# TSC8-75.net
KiCad netlist of a schematic drawn in EAGLE
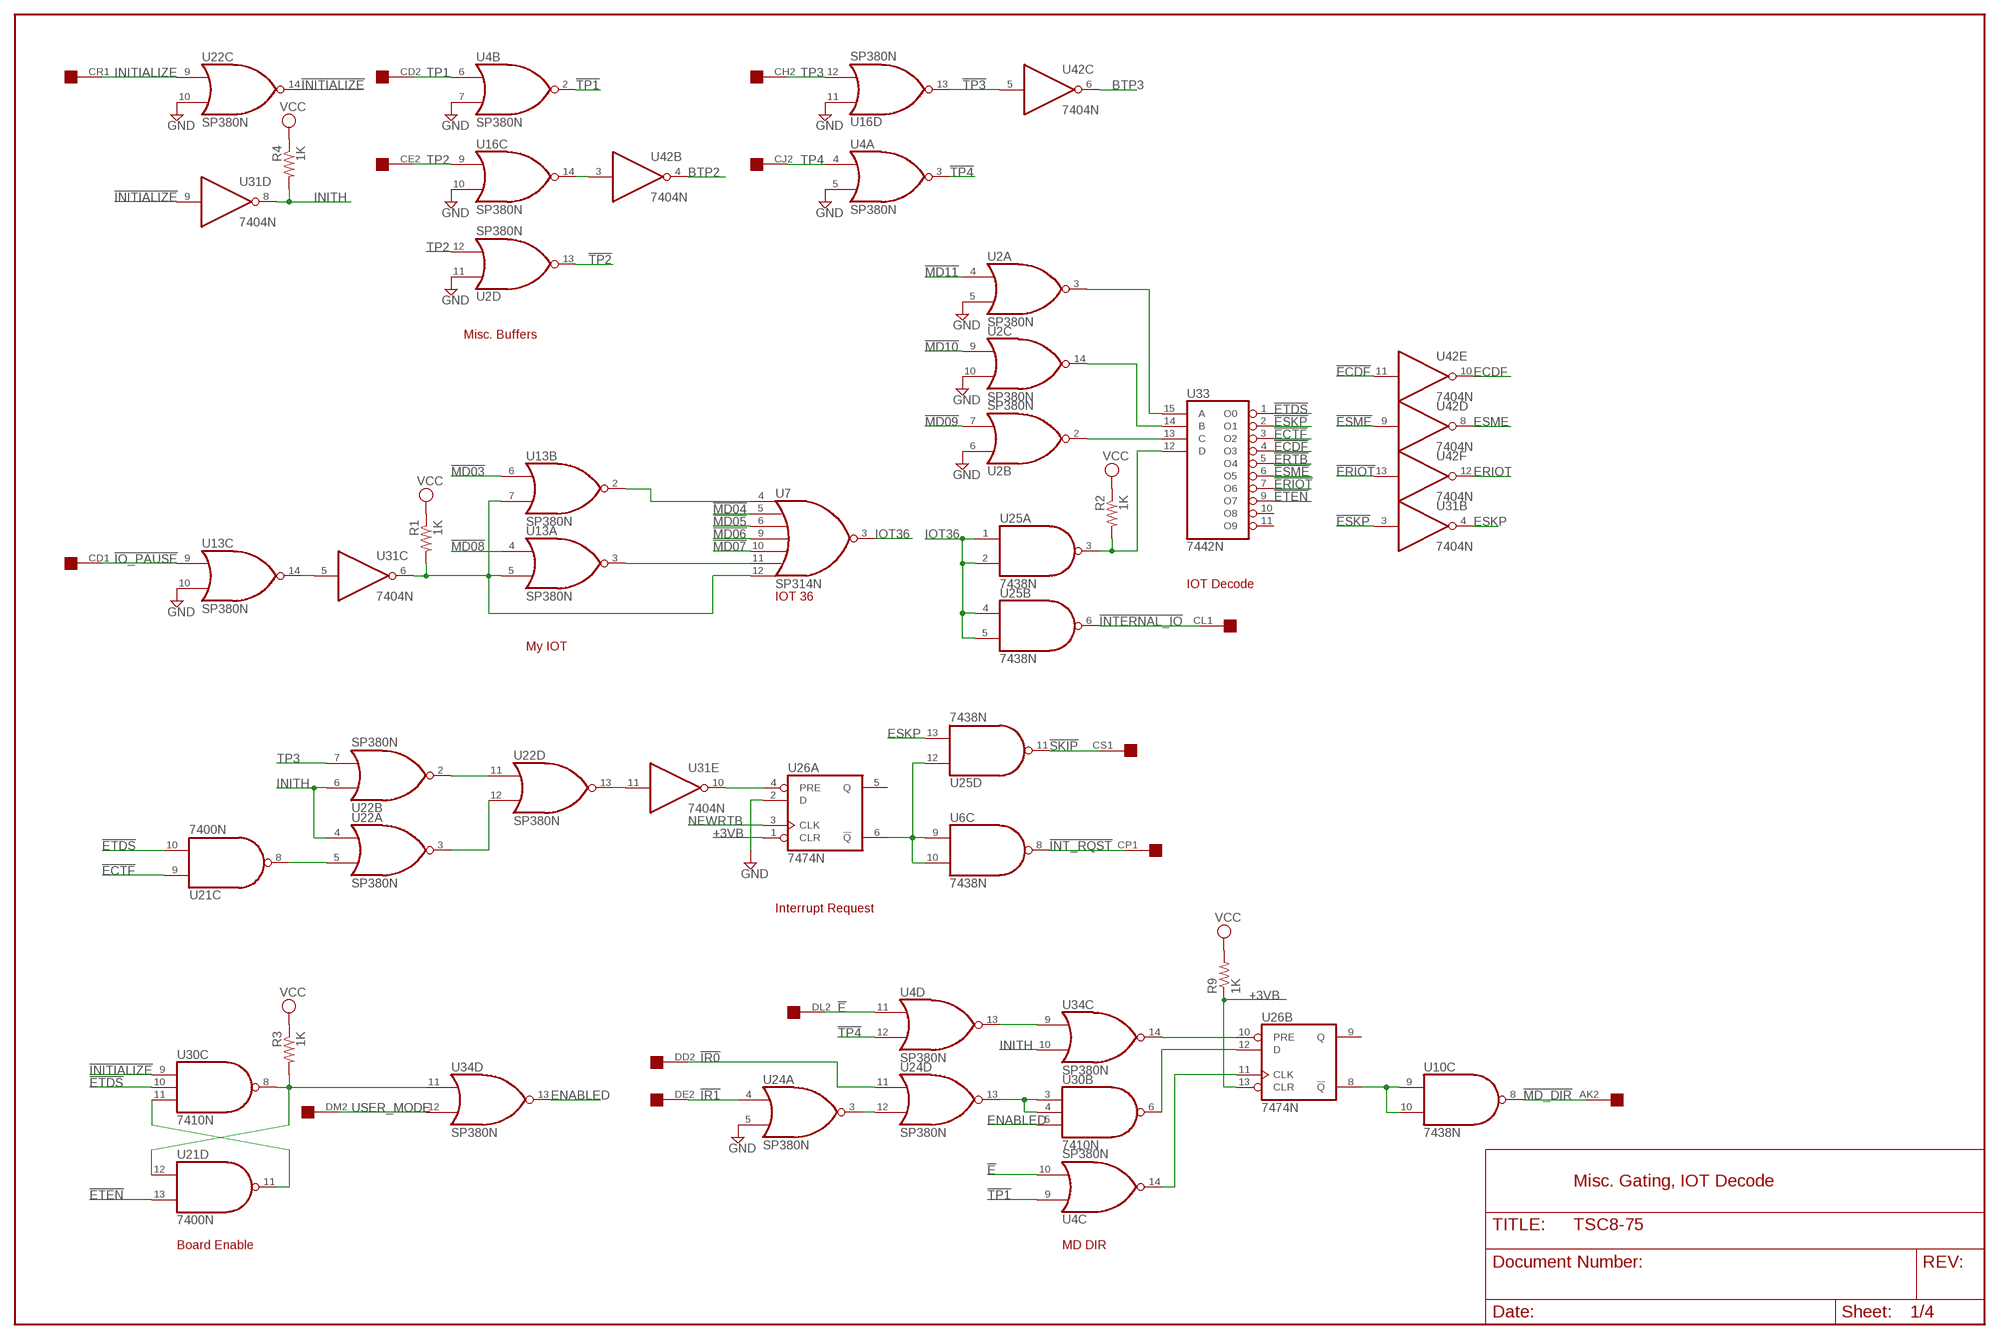
[diagram p0: schematic, sheet 1]
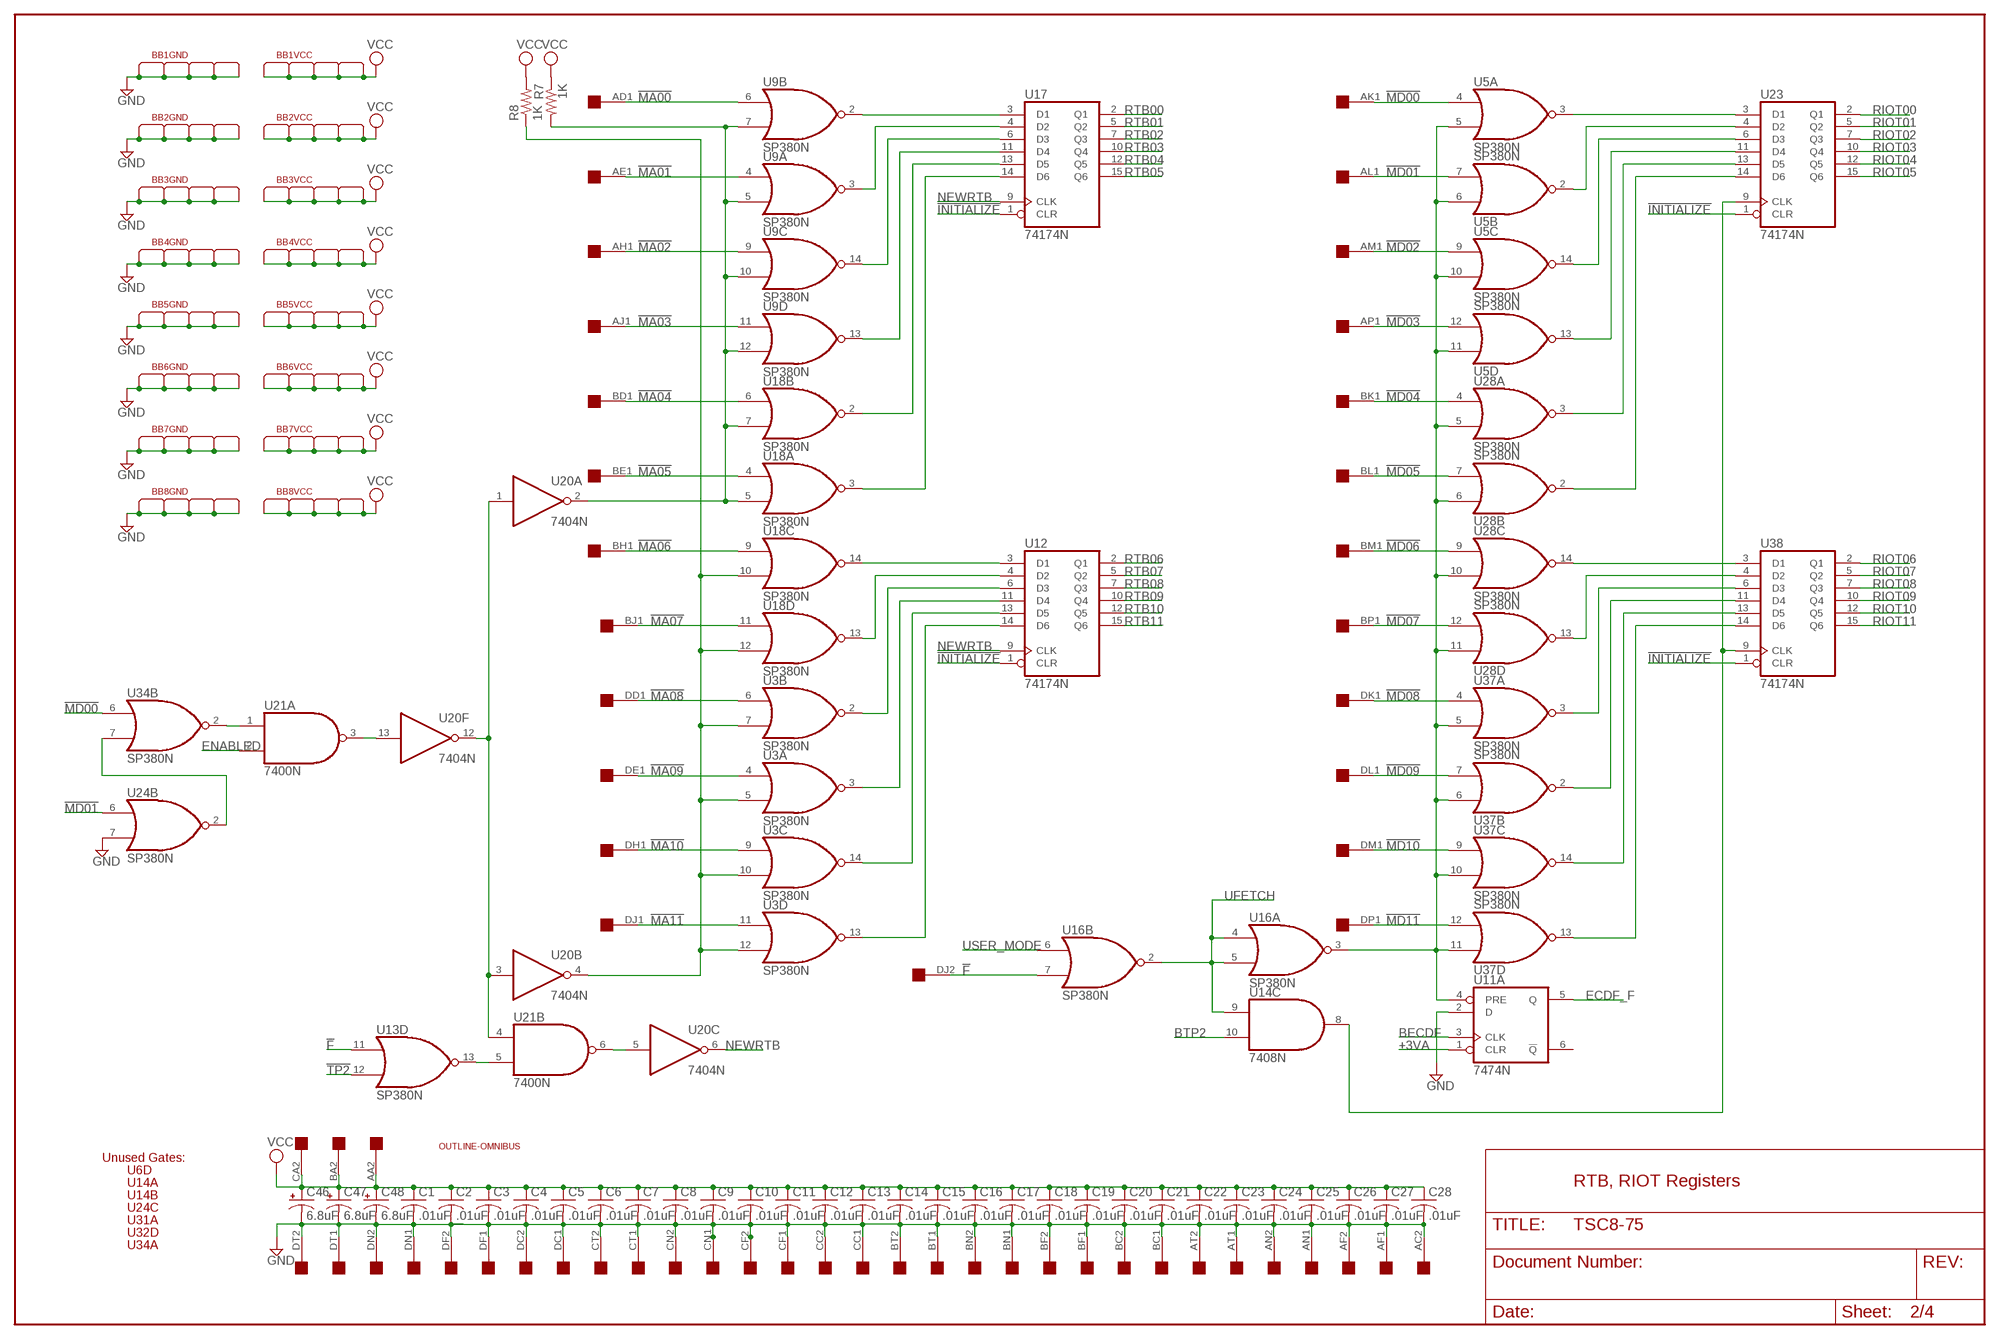
[diagram p1: schematic, sheet 2]
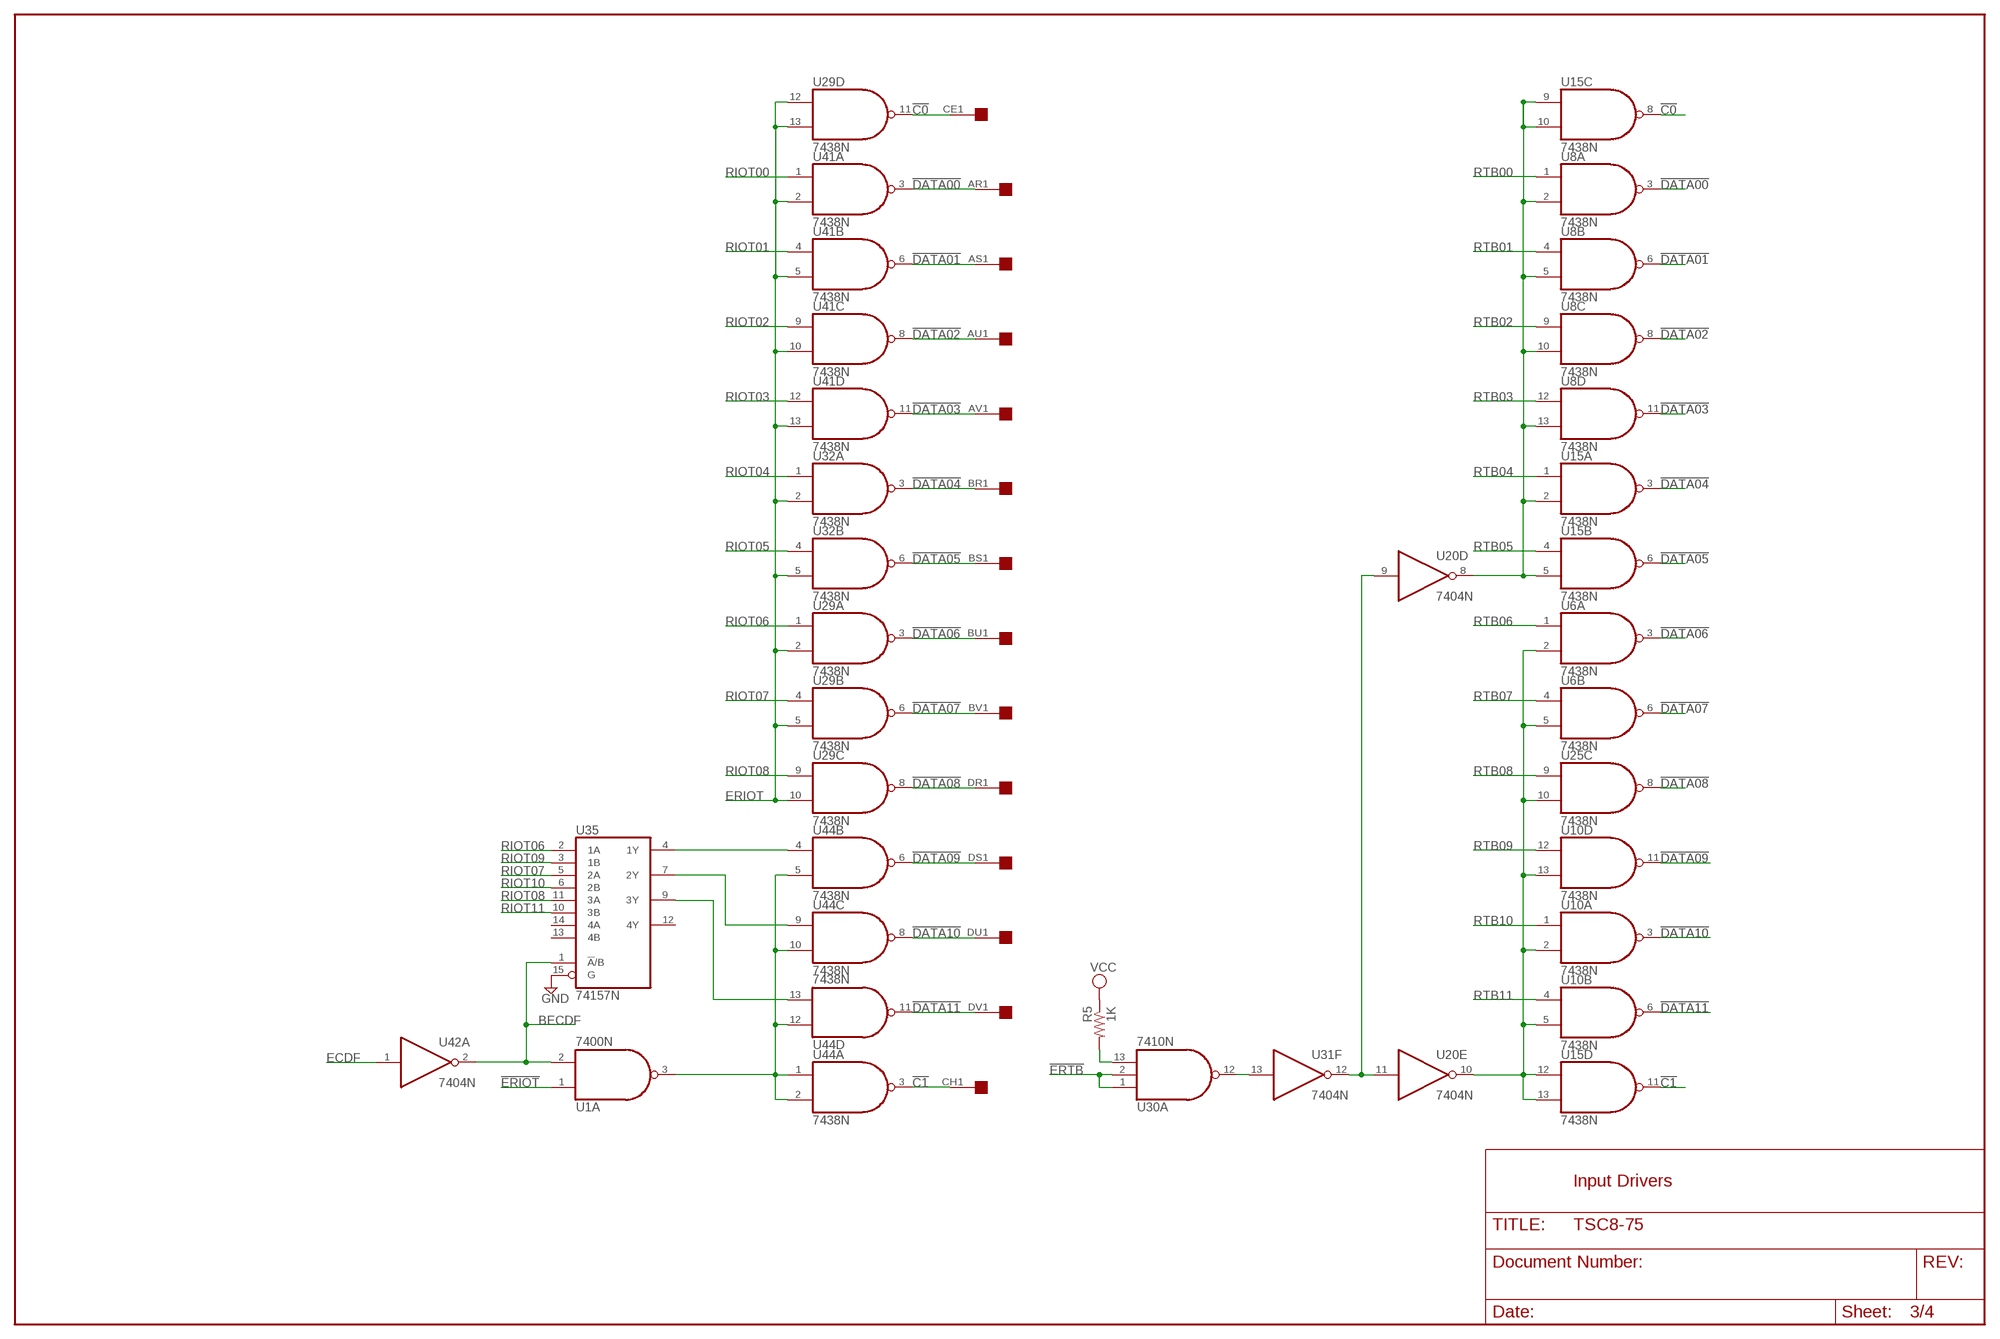
[diagram p2: schematic, sheet 3]
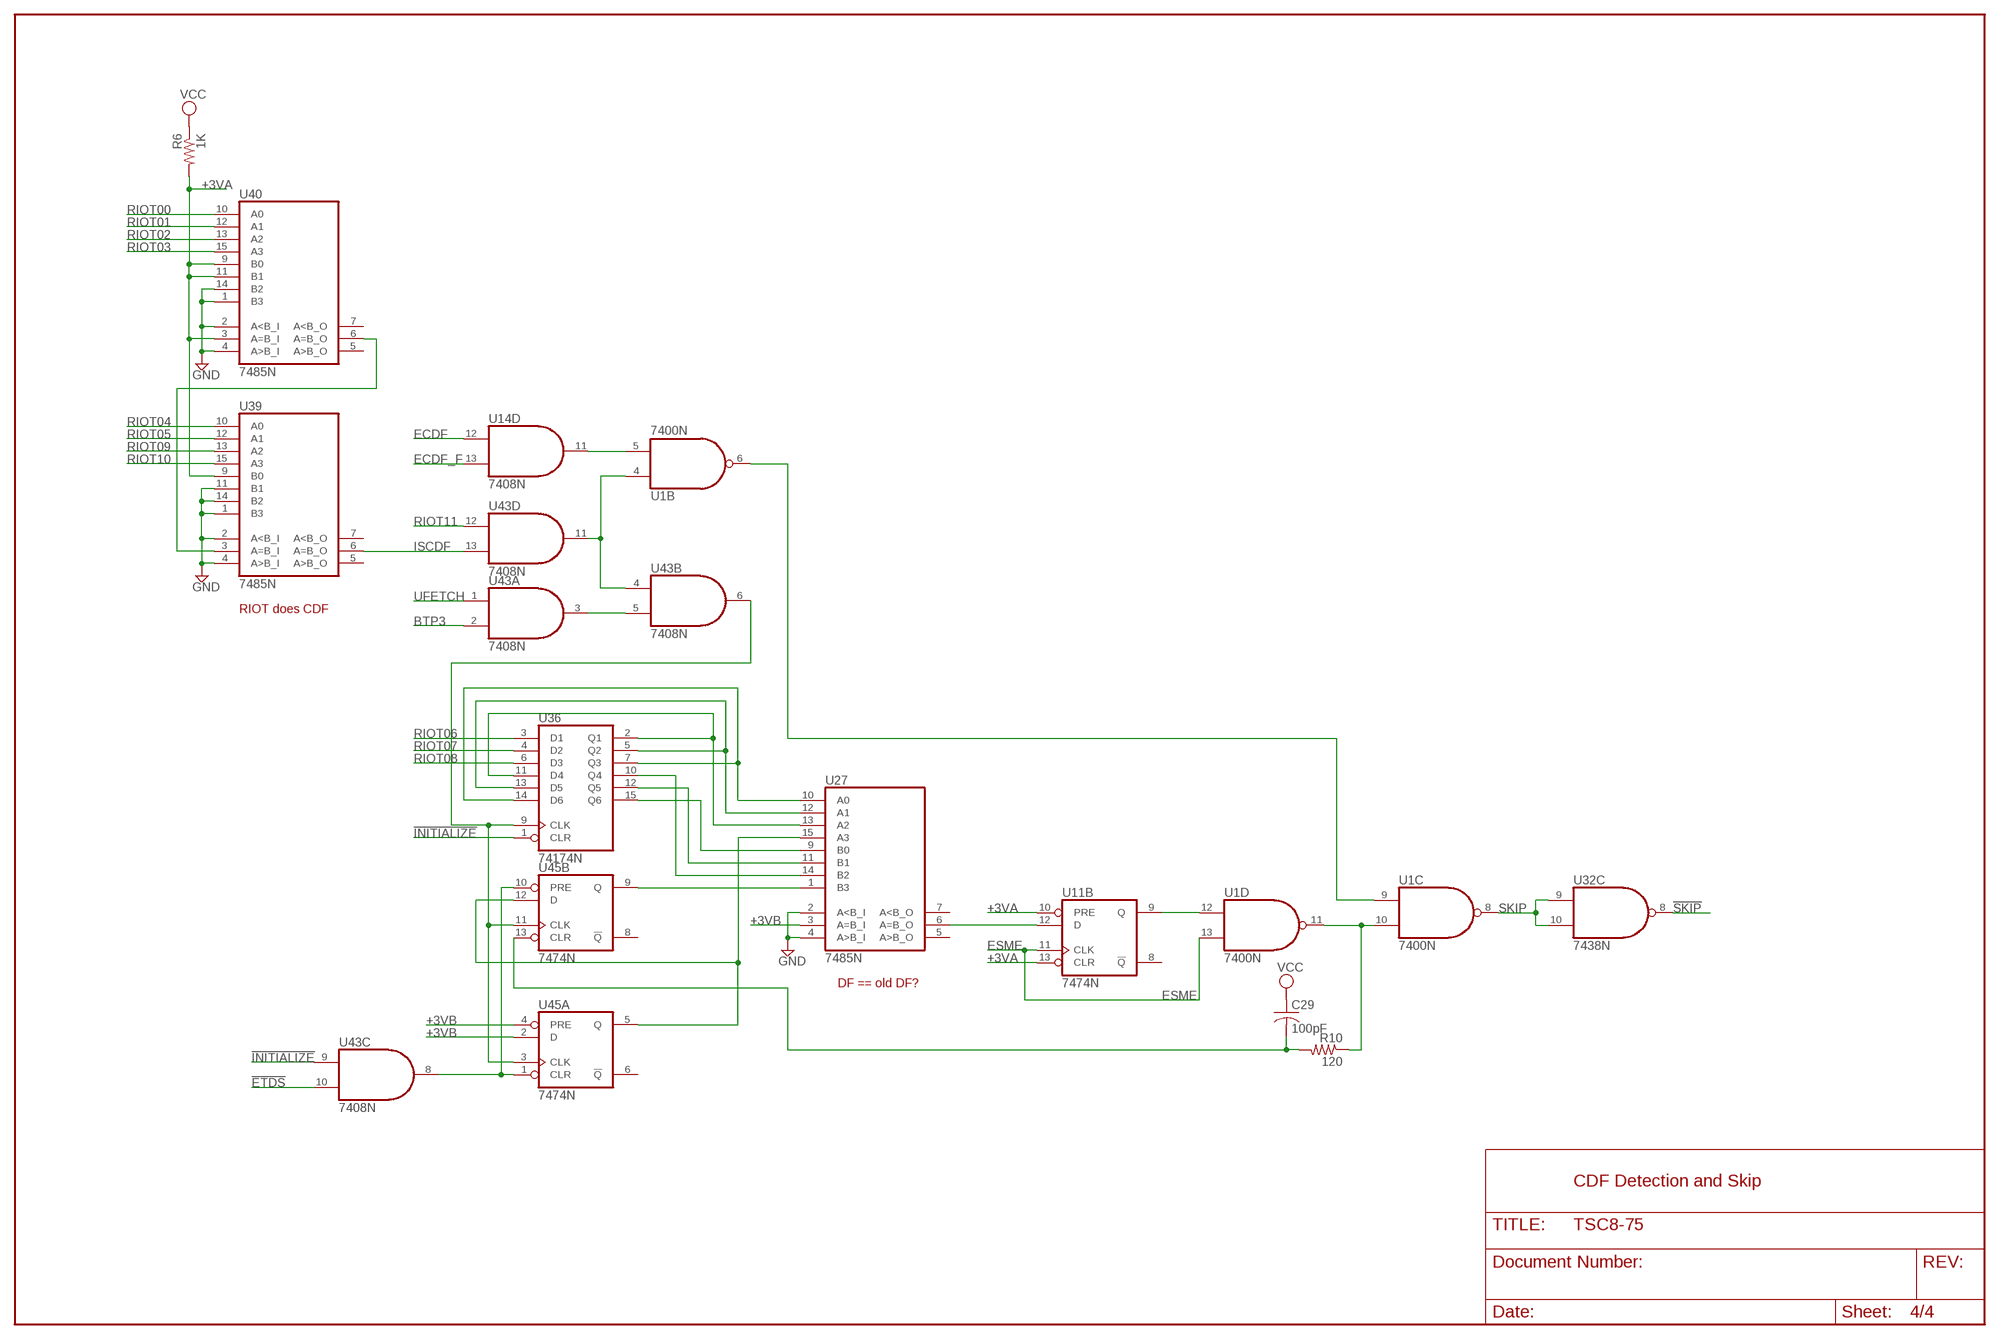
[diagram p3: schematic, sheet 4]

(export (version "E")
  (design (tool "Eeschema 10.0.6"))
  (components
    (comp (ref "BB1")
      (value "BUSBAR")
      (footprint "eagle-import:BUSBAR")
      (libsource (lib "eagle-import") (part "BUSBAR"))
    )
    (comp (ref "BB2")
      (value "BUSBAR")
      (footprint "eagle-import:BUSBAR")
      (libsource (lib "eagle-import") (part "BUSBAR"))
    )
    (comp (ref "BB3")
      (value "BUSBAR")
      (footprint "eagle-import:BUSBAR")
      (libsource (lib "eagle-import") (part "BUSBAR"))
    )
    (comp (ref "BB4")
      (value "BUSBAR")
      (footprint "eagle-import:BUSBAR")
      (libsource (lib "eagle-import") (part "BUSBAR"))
    )
    (comp (ref "BB5")
      (value "BUSBAR")
      (footprint "eagle-import:BUSBAR")
      (libsource (lib "eagle-import") (part "BUSBAR"))
    )
    (comp (ref "BB6")
      (value "BUSBAR")
      (footprint "eagle-import:BUSBAR")
      (libsource (lib "eagle-import") (part "BUSBAR"))
    )
    (comp (ref "BB7")
      (value "BUSBAR")
      (footprint "eagle-import:BUSBAR")
      (libsource (lib "eagle-import") (part "BUSBAR"))
    )
    (comp (ref "BB8")
      (value "BUSBAR")
      (footprint "eagle-import:BUSBAR")
      (libsource (lib "eagle-import") (part "BUSBAR"))
    )
    (comp (ref "C1")
      (value ".01uF")
      (footprint "eagle-import:C050-025X075")
      (libsource (lib "eagle-import") (part "C-US050-025X075"))
    )
    (comp (ref "C2")
      (value ".01uF")
      (footprint "eagle-import:C050-025X075")
      (libsource (lib "eagle-import") (part "C-US050-025X075"))
    )
    (comp (ref "C3")
      (value ".01uF")
      (footprint "eagle-import:C050-025X075")
      (libsource (lib "eagle-import") (part "C-US050-025X075"))
    )
    (comp (ref "C4")
      (value ".01uF")
      (footprint "eagle-import:C050-025X075")
      (libsource (lib "eagle-import") (part "C-US050-025X075"))
    )
    (comp (ref "C5")
      (value ".01uF")
      (footprint "eagle-import:C050-025X075")
      (libsource (lib "eagle-import") (part "C-US050-025X075"))
    )
    (comp (ref "C6")
      (value ".01uF")
      (footprint "eagle-import:C050-025X075")
      (libsource (lib "eagle-import") (part "C-US050-025X075"))
    )
    (comp (ref "C7")
      (value ".01uF")
      (footprint "eagle-import:C050-025X075")
      (libsource (lib "eagle-import") (part "C-US050-025X075"))
    )
    (comp (ref "C8")
      (value ".01uF")
      (footprint "eagle-import:C050-025X075")
      (libsource (lib "eagle-import") (part "C-US050-025X075"))
    )
    (comp (ref "C9")
      (value ".01uF")
      (footprint "eagle-import:C050-025X075")
      (libsource (lib "eagle-import") (part "C-US050-025X075"))
    )
    (comp (ref "C10")
      (value ".01uF")
      (footprint "eagle-import:C050-025X075")
      (libsource (lib "eagle-import") (part "C-US050-025X075"))
    )
    (comp (ref "C11")
      (value ".01uF")
      (footprint "eagle-import:C050-025X075")
      (libsource (lib "eagle-import") (part "C-US050-025X075"))
    )
    (comp (ref "C12")
      (value ".01uF")
      (footprint "eagle-import:C050-025X075")
      (libsource (lib "eagle-import") (part "C-US050-025X075"))
    )
    (comp (ref "C13")
      (value ".01uF")
      (footprint "eagle-import:C050-025X075")
      (libsource (lib "eagle-import") (part "C-US050-025X075"))
    )
    (comp (ref "C14")
      (value ".01uF")
      (footprint "eagle-import:C050-025X075")
      (libsource (lib "eagle-import") (part "C-US050-025X075"))
    )
    (comp (ref "C15")
      (value ".01uF")
      (footprint "eagle-import:C050-025X075")
      (libsource (lib "eagle-import") (part "C-US050-025X075"))
    )
    (comp (ref "C16")
      (value ".01uF")
      (footprint "eagle-import:C050-025X075")
      (libsource (lib "eagle-import") (part "C-US050-025X075"))
    )
    (comp (ref "C17")
      (value ".01uF")
      (footprint "eagle-import:C050-025X075")
      (libsource (lib "eagle-import") (part "C-US050-025X075"))
    )
    (comp (ref "C18")
      (value ".01uF")
      (footprint "eagle-import:C050-025X075")
      (libsource (lib "eagle-import") (part "C-US050-025X075"))
    )
    (comp (ref "C19")
      (value ".01uF")
      (footprint "eagle-import:C050-025X075")
      (libsource (lib "eagle-import") (part "C-US050-025X075"))
    )
    (comp (ref "C20")
      (value ".01uF")
      (footprint "eagle-import:C050-025X075")
      (libsource (lib "eagle-import") (part "C-US050-025X075"))
    )
    (comp (ref "C21")
      (value ".01uF")
      (footprint "eagle-import:C050-025X075")
      (libsource (lib "eagle-import") (part "C-US050-025X075"))
    )
    (comp (ref "C22")
      (value ".01uF")
      (footprint "eagle-import:C050-025X075")
      (libsource (lib "eagle-import") (part "C-US050-025X075"))
    )
    (comp (ref "C23")
      (value ".01uF")
      (footprint "eagle-import:C050-025X075")
      (libsource (lib "eagle-import") (part "C-US050-025X075"))
    )
    (comp (ref "C24")
      (value ".01uF")
      (footprint "eagle-import:C050-025X075")
      (libsource (lib "eagle-import") (part "C-US050-025X075"))
    )
    (comp (ref "C25")
      (value ".01uF")
      (footprint "eagle-import:C050-025X075")
      (libsource (lib "eagle-import") (part "C-US050-025X075"))
    )
    (comp (ref "C26")
      (value ".01uF")
      (footprint "eagle-import:C050-025X075")
      (libsource (lib "eagle-import") (part "C-US050-025X075"))
    )
    (comp (ref "C27")
      (value ".01uF")
      (footprint "eagle-import:C050-025X075")
      (libsource (lib "eagle-import") (part "C-US050-025X075"))
    )
    (comp (ref "C28")
      (value ".01uF")
      (footprint "eagle-import:C050-025X075")
      (libsource (lib "eagle-import") (part "C-US050-025X075"))
    )
    (comp (ref "C46")
      (value "6.8uF")
      (footprint "eagle-import:E12-8")
      (libsource (lib "eagle-import") (part "CPOL-USE20-8AXIAL"))
    )
    (comp (ref "C47")
      (value "6.8uF")
      (footprint "eagle-import:E12-8")
      (libsource (lib "eagle-import") (part "CPOL-USE20-8AXIAL"))
    )
    (comp (ref "C48")
      (value "6.8uF")
      (footprint "eagle-import:E12-8")
      (libsource (lib "eagle-import") (part "CPOL-USE20-8AXIAL"))
    )
    (comp (ref "EDGE")
      (value "edge")
      (footprint "eagle-import:EDGE-CON8")
      (libsource (lib "eagle-import") (part "QUAD"))
    )
    (comp (ref "R7")
      (value "1K")
      (footprint "eagle-import:0204_7")
      (libsource (lib "eagle-import") (part "R-US_0204/7"))
    )
    (comp (ref "R8")
      (value "1K")
      (footprint "eagle-import:0204_7")
      (libsource (lib "eagle-import") (part "R-US_0204/7"))
    )
    (comp (ref "U$1")
      (value "OUTLINE-OMNIBUS")
      (footprint "eagle-import:OMNIBUS")
      (libsource (lib "eagle-import") (part "OUTLINE-OMNIBUS"))
    )
    (comp (ref "U3")
      (value "SP380N")
      (footprint "eagle-import:DIL14")
      (libsource (lib "eagle-import") (part "SP380N"))
    )
    (comp (ref "U5")
      (value "SP380N")
      (footprint "eagle-import:DIL14")
      (libsource (lib "eagle-import") (part "SP380N"))
    )
    (comp (ref "U9")
      (value "SP380N")
      (footprint "eagle-import:DIL14")
      (libsource (lib "eagle-import") (part "SP380N"))
    )
    (comp (ref "U11")
      (value "7474N")
      (footprint "eagle-import:DIL14")
      (libsource (lib "eagle-import") (part "7474NS"))
    )
    (comp (ref "U12")
      (value "74174N")
      (footprint "eagle-import:DIL16")
      (libsource (lib "eagle-import") (part "74174N"))
    )
    (comp (ref "U13")
      (value "SP380N")
      (footprint "eagle-import:DIL14")
      (libsource (lib "eagle-import") (part "SP380N"))
    )
    (comp (ref "U14")
      (value "7408N")
      (footprint "eagle-import:DIL14")
      (libsource (lib "eagle-import") (part "7408NS"))
    )
    (comp (ref "U16")
      (value "SP380N")
      (footprint "eagle-import:DIL14")
      (libsource (lib "eagle-import") (part "SP380N"))
    )
    (comp (ref "U17")
      (value "74174N")
      (footprint "eagle-import:DIL16")
      (libsource (lib "eagle-import") (part "74174N"))
    )
    (comp (ref "U18")
      (value "SP380N")
      (footprint "eagle-import:DIL14")
      (libsource (lib "eagle-import") (part "SP380N"))
    )
    (comp (ref "U20")
      (value "7404N")
      (footprint "eagle-import:DIL14")
      (libsource (lib "eagle-import") (part "7404N"))
    )
    (comp (ref "U21")
      (value "7400N")
      (footprint "eagle-import:DIL14")
      (libsource (lib "eagle-import") (part "7400N"))
    )
    (comp (ref "U23")
      (value "74174N")
      (footprint "eagle-import:DIL16")
      (libsource (lib "eagle-import") (part "74174N"))
    )
    (comp (ref "U24")
      (value "SP380N")
      (footprint "eagle-import:DIL14")
      (libsource (lib "eagle-import") (part "SP380N"))
    )
    (comp (ref "U28")
      (value "SP380N")
      (footprint "eagle-import:DIL14")
      (libsource (lib "eagle-import") (part "SP380N"))
    )
    (comp (ref "U34")
      (value "SP380N")
      (footprint "eagle-import:DIL14")
      (libsource (lib "eagle-import") (part "SP380N"))
    )
    (comp (ref "U37")
      (value "SP380N")
      (footprint "eagle-import:DIL14")
      (libsource (lib "eagle-import") (part "SP380N"))
    )
    (comp (ref "U38")
      (value "74174N")
      (footprint "eagle-import:DIL16")
      (libsource (lib "eagle-import") (part "74174N"))
    )
    (comp (ref "C29")
      (value "100pF")
      (footprint "eagle-import:C050-025X075")
      (libsource (lib "eagle-import") (part "C-US050-025X075"))
    )
    (comp (ref "R6")
      (value "1K")
      (footprint "eagle-import:0204_7")
      (libsource (lib "eagle-import") (part "R-US_0204/7"))
    )
    (comp (ref "R10")
      (value "120")
      (footprint "eagle-import:0204_7")
      (libsource (lib "eagle-import") (part "R-US_0204/7"))
    )
    (comp (ref "U1")
      (value "7400N")
      (footprint "eagle-import:DIL14")
      (libsource (lib "eagle-import") (part "7400N"))
    )
    (comp (ref "U27")
      (value "7485N")
      (footprint "eagle-import:DIL16")
      (libsource (lib "eagle-import") (part "7485N"))
    )
    (comp (ref "U32")
      (value "7438N")
      (footprint "eagle-import:DIL14")
      (libsource (lib "eagle-import") (part "7438N"))
    )
    (comp (ref "U36")
      (value "74174N")
      (footprint "eagle-import:DIL16")
      (libsource (lib "eagle-import") (part "74174N"))
    )
    (comp (ref "U39")
      (value "7485N")
      (footprint "eagle-import:DIL16")
      (libsource (lib "eagle-import") (part "7485N"))
    )
    (comp (ref "U40")
      (value "7485N")
      (footprint "eagle-import:DIL16")
      (libsource (lib "eagle-import") (part "7485N"))
    )
    (comp (ref "U43")
      (value "7408N")
      (footprint "eagle-import:DIL14")
      (libsource (lib "eagle-import") (part "7408NS"))
    )
    (comp (ref "U45")
      (value "7474N")
      (footprint "eagle-import:DIL14")
      (libsource (lib "eagle-import") (part "7474NS"))
    )
    (comp (ref "R1")
      (value "1K")
      (footprint "eagle-import:0204_7")
      (libsource (lib "eagle-import") (part "R-US_0204/7"))
    )
    (comp (ref "R2")
      (value "1K")
      (footprint "eagle-import:0204_7")
      (libsource (lib "eagle-import") (part "R-US_0204/7"))
    )
    (comp (ref "R3")
      (value "1K")
      (footprint "eagle-import:0204_7")
      (libsource (lib "eagle-import") (part "R-US_0204/7"))
    )
    (comp (ref "R4")
      (value "1K")
      (footprint "eagle-import:0204_7")
      (libsource (lib "eagle-import") (part "R-US_0204/7"))
    )
    (comp (ref "R9")
      (value "1K")
      (footprint "eagle-import:0204_7")
      (libsource (lib "eagle-import") (part "R-US_0204/7"))
    )
    (comp (ref "U2")
      (value "SP380N")
      (footprint "eagle-import:DIL14")
      (libsource (lib "eagle-import") (part "SP380N"))
    )
    (comp (ref "U4")
      (value "SP380N")
      (footprint "eagle-import:DIL14")
      (libsource (lib "eagle-import") (part "SP380N"))
    )
    (comp (ref "U6")
      (value "7438N")
      (footprint "eagle-import:DIL14")
      (libsource (lib "eagle-import") (part "7438N"))
    )
    (comp (ref "U7")
      (value "SP314N")
      (footprint "eagle-import:DIL14")
      (libsource (lib "eagle-import") (part "SP314N"))
    )
    (comp (ref "U10")
      (value "7438N")
      (footprint "eagle-import:DIL14")
      (libsource (lib "eagle-import") (part "7438N"))
    )
    (comp (ref "U22")
      (value "SP380N")
      (footprint "eagle-import:DIL14")
      (libsource (lib "eagle-import") (part "SP380N"))
    )
    (comp (ref "U25")
      (value "7438N")
      (footprint "eagle-import:DIL14")
      (libsource (lib "eagle-import") (part "7438N"))
    )
    (comp (ref "U26")
      (value "7474N")
      (footprint "eagle-import:DIL14")
      (libsource (lib "eagle-import") (part "7474NS"))
    )
    (comp (ref "U30")
      (value "7410N")
      (footprint "eagle-import:DIL14")
      (libsource (lib "eagle-import") (part "7410N"))
    )
    (comp (ref "U31")
      (value "7404N")
      (footprint "eagle-import:DIL14")
      (libsource (lib "eagle-import") (part "7404N"))
    )
    (comp (ref "U33")
      (value "7442N")
      (footprint "eagle-import:DIL16")
      (libsource (lib "eagle-import") (part "7442NLS"))
    )
    (comp (ref "U42")
      (value "7404N")
      (footprint "eagle-import:DIL14")
      (libsource (lib "eagle-import") (part "7404N"))
    )
    (comp (ref "R5")
      (value "1K")
      (footprint "eagle-import:0204_7")
      (libsource (lib "eagle-import") (part "R-US_0204/7"))
    )
    (comp (ref "U8")
      (value "7438N")
      (footprint "eagle-import:DIL14")
      (libsource (lib "eagle-import") (part "7438N"))
    )
    (comp (ref "U15")
      (value "7438N")
      (footprint "eagle-import:DIL14")
      (libsource (lib "eagle-import") (part "7438N"))
    )
    (comp (ref "U29")
      (value "7438N")
      (footprint "eagle-import:DIL14")
      (libsource (lib "eagle-import") (part "7438N"))
    )
    (comp (ref "U35")
      (value "74157N")
      (footprint "eagle-import:DIL16")
      (libsource (lib "eagle-import") (part "74157N"))
    )
    (comp (ref "U41")
      (value "7438N")
      (footprint "eagle-import:DIL14")
      (libsource (lib "eagle-import") (part "7438N"))
    )
    (comp (ref "U44")
      (value "7438N")
      (footprint "eagle-import:DIL14")
      (libsource (lib "eagle-import") (part "7438N"))
    )
  )
  (nets
    (net (code "1") (name "+3VA") (class "Default")
      (node (ref "R6") (pin "2") (pinfunction "2_2") (pintype "passive"))
      (node (ref "U11") (pin "1") (pinfunction "CLR_1") (pintype "input"))
      (node (ref "U11") (pin "10") (pinfunction "PRE_10") (pintype "input"))
      (node (ref "U11") (pin "13") (pinfunction "CLR_13") (pintype "input"))
      (node (ref "U39") (pin "9") (pinfunction "B0_9") (pintype "input"))
      (node (ref "U40") (pin "11") (pinfunction "B1_11") (pintype "input"))
      (node (ref "U40") (pin "3") (pinfunction "A=B_I_3") (pintype "input"))
      (node (ref "U40") (pin "9") (pinfunction "B0_9") (pintype "input"))
    )
    (net (code "2") (name "+3VB") (class "Default")
      (node (ref "R9") (pin "1") (pinfunction "1_1") (pintype "passive"))
      (node (ref "U26") (pin "1") (pinfunction "CLR_1") (pintype "input"))
      (node (ref "U26") (pin "13") (pinfunction "CLR_13") (pintype "input"))
      (node (ref "U27") (pin "3") (pinfunction "A=B_I_3") (pintype "input"))
      (node (ref "U45") (pin "2") (pinfunction "D_2") (pintype "input"))
      (node (ref "U45") (pin "4") (pinfunction "PRE_4") (pintype "input"))
    )
    (net (code "3") (name "BECDF") (class "Default")
      (node (ref "U1") (pin "2") (pinfunction "I1_2") (pintype "input"))
      (node (ref "U11") (pin "3") (pinfunction "CLK_3") (pintype "input"))
      (node (ref "U35") (pin "1") (pinfunction "~{A}/B_1") (pintype "input"))
      (node (ref "U42") (pin "2") (pinfunction "O_2") (pintype "output"))
    )
    (net (code "4") (name "BTP2") (class "Default")
      (node (ref "U14") (pin "10") (pinfunction "I1_10") (pintype "input"))
      (node (ref "U42") (pin "4") (pinfunction "O_4") (pintype "output"))
    )
    (net (code "5") (name "BTP3") (class "Default")
      (node (ref "U42") (pin "6") (pinfunction "O_6") (pintype "output"))
      (node (ref "U43") (pin "2") (pinfunction "I1_2") (pintype "input"))
    )
    (net (code "6") (name "ECDF") (class "Default")
      (node (ref "U14") (pin "12") (pinfunction "I0_12") (pintype "input"))
      (node (ref "U42") (pin "1") (pinfunction "I_1") (pintype "input"))
      (node (ref "U42") (pin "10") (pinfunction "O_10") (pintype "output"))
    )
    (net (code "7") (name "ECDF_F") (class "Default")
      (node (ref "U11") (pin "5") (pinfunction "Q_5") (pintype "output"))
      (node (ref "U14") (pin "13") (pinfunction "I1_13") (pintype "input"))
    )
    (net (code "8") (name "ENABLED") (class "Default")
      (node (ref "U21") (pin "2") (pinfunction "I1_2") (pintype "input"))
      (node (ref "U30") (pin "5") (pinfunction "I2_5") (pintype "input"))
      (node (ref "U34") (pin "13") (pinfunction "O_13") (pintype "output"))
    )
    (net (code "9") (name "ERIOT") (class "Default")
      (node (ref "U29") (pin "10") (pinfunction "I1_10") (pintype "input"))
      (node (ref "U29") (pin "12") (pinfunction "I0_12") (pintype "input"))
      (node (ref "U29") (pin "13") (pinfunction "I1_13") (pintype "input"))
      (node (ref "U29") (pin "2") (pinfunction "I1_2") (pintype "input"))
      (node (ref "U29") (pin "5") (pinfunction "I1_5") (pintype "input"))
      (node (ref "U32") (pin "2") (pinfunction "I1_2") (pintype "input"))
      (node (ref "U32") (pin "5") (pinfunction "I1_5") (pintype "input"))
      (node (ref "U41") (pin "10") (pinfunction "I1_10") (pintype "input"))
      (node (ref "U41") (pin "13") (pinfunction "I1_13") (pintype "input"))
      (node (ref "U41") (pin "2") (pinfunction "I1_2") (pintype "input"))
      (node (ref "U41") (pin "5") (pinfunction "I1_5") (pintype "input"))
      (node (ref "U42") (pin "12") (pinfunction "O_12") (pintype "output"))
    )
    (net (code "10") (name "ESKP") (class "Default")
      (node (ref "U25") (pin "13") (pinfunction "I1_13") (pintype "input"))
      (node (ref "U31") (pin "4") (pinfunction "O_4") (pintype "output"))
    )
    (net (code "11") (name "ESME") (class "Default")
      (node (ref "U1") (pin "13") (pinfunction "I1_13") (pintype "input"))
      (node (ref "U11") (pin "11") (pinfunction "CLK_11") (pintype "input"))
      (node (ref "U42") (pin "8") (pinfunction "O_8") (pintype "output"))
    )
    (net (code "12") (name "GND") (class "Default")
      (node (ref "BB1") (pin "GND1") (pinfunction "1_GND1") (pintype "passive"))
      (node (ref "BB1") (pin "GND2") (pinfunction "2_GND2") (pintype "passive"))
      (node (ref "BB1") (pin "GND3") (pinfunction "3_GND3") (pintype "passive"))
      (node (ref "BB1") (pin "GND4") (pinfunction "4_GND4") (pintype "passive"))
      (node (ref "BB1") (pin "GND5") (pinfunction "5_GND5") (pintype "passive"))
      (node (ref "BB2") (pin "GND1") (pinfunction "1_GND1") (pintype "passive"))
      (node (ref "BB2") (pin "GND2") (pinfunction "2_GND2") (pintype "passive"))
      (node (ref "BB2") (pin "GND3") (pinfunction "3_GND3") (pintype "passive"))
      (node (ref "BB2") (pin "GND4") (pinfunction "4_GND4") (pintype "passive"))
      (node (ref "BB2") (pin "GND5") (pinfunction "5_GND5") (pintype "passive"))
      (node (ref "BB3") (pin "GND1") (pinfunction "1_GND1") (pintype "passive"))
      (node (ref "BB3") (pin "GND2") (pinfunction "2_GND2") (pintype "passive"))
      (node (ref "BB3") (pin "GND3") (pinfunction "3_GND3") (pintype "passive"))
      (node (ref "BB3") (pin "GND4") (pinfunction "4_GND4") (pintype "passive"))
      (node (ref "BB3") (pin "GND5") (pinfunction "5_GND5") (pintype "passive"))
      (node (ref "BB4") (pin "GND1") (pinfunction "1_GND1") (pintype "passive"))
      (node (ref "BB4") (pin "GND2") (pinfunction "2_GND2") (pintype "passive"))
      (node (ref "BB4") (pin "GND3") (pinfunction "3_GND3") (pintype "passive"))
      (node (ref "BB4") (pin "GND4") (pinfunction "4_GND4") (pintype "passive"))
      (node (ref "BB4") (pin "GND5") (pinfunction "5_GND5") (pintype "passive"))
      (node (ref "BB5") (pin "GND1") (pinfunction "1_GND1") (pintype "passive"))
      (node (ref "BB5") (pin "GND2") (pinfunction "2_GND2") (pintype "passive"))
      (node (ref "BB5") (pin "GND3") (pinfunction "3_GND3") (pintype "passive"))
      (node (ref "BB5") (pin "GND4") (pinfunction "4_GND4") (pintype "passive"))
      (node (ref "BB5") (pin "GND5") (pinfunction "5_GND5") (pintype "passive"))
      (node (ref "BB6") (pin "GND1") (pinfunction "1_GND1") (pintype "passive"))
      (node (ref "BB6") (pin "GND2") (pinfunction "2_GND2") (pintype "passive"))
      (node (ref "BB6") (pin "GND3") (pinfunction "3_GND3") (pintype "passive"))
      (node (ref "BB6") (pin "GND4") (pinfunction "4_GND4") (pintype "passive"))
      (node (ref "BB6") (pin "GND5") (pinfunction "5_GND5") (pintype "passive"))
      (node (ref "BB7") (pin "GND1") (pinfunction "1_GND1") (pintype "passive"))
      (node (ref "BB7") (pin "GND2") (pinfunction "2_GND2") (pintype "passive"))
      (node (ref "BB7") (pin "GND3") (pinfunction "3_GND3") (pintype "passive"))
      (node (ref "BB7") (pin "GND4") (pinfunction "4_GND4") (pintype "passive"))
      (node (ref "BB7") (pin "GND5") (pinfunction "5_GND5") (pintype "passive"))
      (node (ref "BB8") (pin "GND1") (pinfunction "1_GND1") (pintype "passive"))
      (node (ref "BB8") (pin "GND2") (pinfunction "2_GND2") (pintype "passive"))
      (node (ref "BB8") (pin "GND3") (pinfunction "3_GND3") (pintype "passive"))
      (node (ref "BB8") (pin "GND4") (pinfunction "4_GND4") (pintype "passive"))
      (node (ref "BB8") (pin "GND5") (pinfunction "5_GND5") (pintype "passive"))
      (node (ref "C1") (pin "2") (pinfunction "2_2") (pintype "passive"))
      (node (ref "C10") (pin "2") (pinfunction "2_2") (pintype "passive"))
      (node (ref "C11") (pin "2") (pinfunction "2_2") (pintype "passive"))
      (node (ref "C12") (pin "2") (pinfunction "2_2") (pintype "passive"))
      (node (ref "C13") (pin "2") (pinfunction "2_2") (pintype "passive"))
      (node (ref "C14") (pin "2") (pinfunction "2_2") (pintype "passive"))
      (node (ref "C15") (pin "2") (pinfunction "2_2") (pintype "passive"))
      (node (ref "C16") (pin "2") (pinfunction "2_2") (pintype "passive"))
      (node (ref "C17") (pin "2") (pinfunction "2_2") (pintype "passive"))
      (node (ref "C18") (pin "2") (pinfunction "2_2") (pintype "passive"))
      (node (ref "C19") (pin "2") (pinfunction "2_2") (pintype "passive"))
      (node (ref "C2") (pin "2") (pinfunction "2_2") (pintype "passive"))
      (node (ref "C20") (pin "2") (pinfunction "2_2") (pintype "passive"))
      (node (ref "C21") (pin "2") (pinfunction "2_2") (pintype "passive"))
      (node (ref "C22") (pin "2") (pinfunction "2_2") (pintype "passive"))
      (node (ref "C23") (pin "2") (pinfunction "2_2") (pintype "passive"))
      (node (ref "C24") (pin "2") (pinfunction "2_2") (pintype "passive"))
      (node (ref "C25") (pin "2") (pinfunction "2_2") (pintype "passive"))
      (node (ref "C26") (pin "2") (pinfunction "2_2") (pintype "passive"))
      (node (ref "C27") (pin "2") (pinfunction "2_2") (pintype "passive"))
      (node (ref "C28") (pin "2") (pinfunction "2_2") (pintype "passive"))
      (node (ref "C3") (pin "2") (pinfunction "2_2") (pintype "passive"))
      (node (ref "C4") (pin "2") (pinfunction "2_2") (pintype "passive"))
      (node (ref "C46") (pin "-") (pinfunction "-_-") (pintype "passive"))
      (node (ref "C47") (pin "-") (pinfunction "-_-") (pintype "passive"))
      (node (ref "C48") (pin "-") (pinfunction "-_-") (pintype "passive"))
      (node (ref "C5") (pin "2") (pinfunction "2_2") (pintype "passive"))
      (node (ref "C6") (pin "2") (pinfunction "2_2") (pintype "passive"))
      (node (ref "C7") (pin "2") (pinfunction "2_2") (pintype "passive"))
      (node (ref "C8") (pin "2") (pinfunction "2_2") (pintype "passive"))
      (node (ref "C9") (pin "2") (pinfunction "2_2") (pintype "passive"))
      (node (ref "EDGE") (pin "AC2") (pinfunction "1_AC2") (pintype "bidirectional"))
      (node (ref "EDGE") (pin "AF1") (pinfunction "1_AF1") (pintype "bidirectional"))
      (node (ref "EDGE") (pin "AF2") (pinfunction "1_AF2") (pintype "bidirectional"))
      (node (ref "EDGE") (pin "AN1") (pinfunction "1_AN1") (pintype "bidirectional"))
      (node (ref "EDGE") (pin "AN2") (pinfunction "1_AN2") (pintype "bidirectional"))
      (node (ref "EDGE") (pin "AT1") (pinfunction "1_AT1") (pintype "bidirectional"))
      (node (ref "EDGE") (pin "AT2") (pinfunction "1_AT2") (pintype "bidirectional"))
      (node (ref "EDGE") (pin "BC1") (pinfunction "1_BC1") (pintype "bidirectional"))
      (node (ref "EDGE") (pin "BC2") (pinfunction "1_BC2") (pintype "bidirectional"))
      (node (ref "EDGE") (pin "BF1") (pinfunction "1_BF1") (pintype "bidirectional"))
      (node (ref "EDGE") (pin "BF2") (pinfunction "1_BF2") (pintype "bidirectional"))
      (node (ref "EDGE") (pin "BN1") (pinfunction "1_BN1") (pintype "bidirectional"))
      (node (ref "EDGE") (pin "BN2") (pinfunction "1_BN2") (pintype "bidirectional"))
      (node (ref "EDGE") (pin "BT1") (pinfunction "1_BT1") (pintype "bidirectional"))
      (node (ref "EDGE") (pin "BT2") (pinfunction "1_BT2") (pintype "bidirectional"))
      (node (ref "EDGE") (pin "CC1") (pinfunction "1_CC1") (pintype "bidirectional"))
      (node (ref "EDGE") (pin "CC2") (pinfunction "1_CC2") (pintype "bidirectional"))
      (node (ref "EDGE") (pin "CF1") (pinfunction "1_CF1") (pintype "bidirectional"))
      (node (ref "EDGE") (pin "CF2") (pinfunction "1_CF2") (pintype "bidirectional"))
      (node (ref "EDGE") (pin "CN1") (pinfunction "1_CN1") (pintype "bidirectional"))
      (node (ref "EDGE") (pin "CN2") (pinfunction "1_CN2") (pintype "bidirectional"))
      (node (ref "EDGE") (pin "CT1") (pinfunction "1_CT1") (pintype "bidirectional"))
      (node (ref "EDGE") (pin "CT2") (pinfunction "1_CT2") (pintype "bidirectional"))
      (node (ref "EDGE") (pin "DC1") (pinfunction "1_DC1") (pintype "bidirectional"))
      (node (ref "EDGE") (pin "DC2") (pinfunction "1_DC2") (pintype "bidirectional"))
      (node (ref "EDGE") (pin "DF1") (pinfunction "1_DF1") (pintype "bidirectional"))
      (node (ref "EDGE") (pin "DF2") (pinfunction "1_DF2") (pintype "bidirectional"))
      (node (ref "EDGE") (pin "DN1") (pinfunction "1_DN1") (pintype "bidirectional"))
      (node (ref "EDGE") (pin "DN2") (pinfunction "1_DN2") (pintype "bidirectional"))
      (node (ref "EDGE") (pin "DT1") (pinfunction "1_DT1") (pintype "bidirectional"))
      (node (ref "EDGE") (pin "DT2") (pinfunction "1_DT2") (pintype "bidirectional"))
      (node (ref "U11") (pin "2") (pinfunction "D_2") (pintype "input"))
      (node (ref "U13") (pin "10") (pinfunction "I1_10") (pintype "input"))
      (node (ref "U16") (pin "10") (pinfunction "I1_10") (pintype "input"))
      (node (ref "U16") (pin "11") (pinfunction "I0_11") (pintype "input"))
      (node (ref "U2") (pin "10") (pinfunction "I1_10") (pintype "input"))
      (node (ref "U2") (pin "11") (pinfunction "I0_11") (pintype "input"))
      (node (ref "U2") (pin "5") (pinfunction "I1_5") (pintype "input"))
      (node (ref "U2") (pin "6") (pinfunction "I0_6") (pintype "input"))
      (node (ref "U22") (pin "10") (pinfunction "I1_10") (pintype "input"))
      (node (ref "U24") (pin "5") (pinfunction "I1_5") (pintype "input"))
      (node (ref "U24") (pin "7") (pinfunction "I1_7") (pintype "input"))
      (node (ref "U26") (pin "2") (pinfunction "D_2") (pintype "input"))
      (node (ref "U27") (pin "2") (pinfunction "A<B_I_2") (pintype "input"))
      (node (ref "U27") (pin "4") (pinfunction "A>B_I_4") (pintype "input"))
      (node (ref "U35") (pin "15") (pinfunction "G_15") (pintype "input"))
      (node (ref "U39") (pin "1") (pinfunction "B3_1") (pintype "input"))
      (node (ref "U39") (pin "11") (pinfunction "B1_11") (pintype "input"))
      (node (ref "U39") (pin "14") (pinfunction "B2_14") (pintype "input"))
      (node (ref "U39") (pin "2") (pinfunction "A<B_I_2") (pintype "input"))
      (node (ref "U39") (pin "4") (pinfunction "A>B_I_4") (pintype "input"))
      (node (ref "U4") (pin "5") (pinfunction "I1_5") (pintype "input"))
      (node (ref "U4") (pin "7") (pinfunction "I1_7") (pintype "input"))
      (node (ref "U40") (pin "1") (pinfunction "B3_1") (pintype "input"))
      (node (ref "U40") (pin "14") (pinfunction "B2_14") (pintype "input"))
      (node (ref "U40") (pin "2") (pinfunction "A<B_I_2") (pintype "input"))
      (node (ref "U40") (pin "4") (pinfunction "A>B_I_4") (pintype "input"))
    )
    (net (code "13") (name "INITH") (class "Default")
      (node (ref "R4") (pin "2") (pinfunction "2_2") (pintype "passive"))
      (node (ref "U22") (pin "4") (pinfunction "I0_4") (pintype "input"))
      (node (ref "U22") (pin "6") (pinfunction "I0_6") (pintype "input"))
      (node (ref "U31") (pin "8") (pinfunction "O_8") (pintype "output"))
      (node (ref "U34") (pin "10") (pinfunction "I1_10") (pintype "input"))
    )
    (net (code "14") (name "INITIALIZE") (class "Default")
      (node (ref "EDGE") (pin "CR1") (pinfunction "1_CR1") (pintype "bidirectional"))
      (node (ref "U22") (pin "9") (pinfunction "I0_9") (pintype "input"))
    )
    (net (code "15") (name "IOT36") (class "Default")
      (node (ref "U25") (pin "1") (pinfunction "I0_1") (pintype "input"))
      (node (ref "U25") (pin "2") (pinfunction "I1_2") (pintype "input"))
      (node (ref "U25") (pin "4") (pinfunction "I0_4") (pintype "input"))
      (node (ref "U25") (pin "5") (pinfunction "I1_5") (pintype "input"))
      (node (ref "U7") (pin "3") (pinfunction "O_3") (pintype "output"))
    )
    (net (code "16") (name "ISCDF") (class "Default")
      (node (ref "U39") (pin "6") (pinfunction "A=B_O_6") (pintype "output"))
      (node (ref "U43") (pin "13") (pinfunction "I1_13") (pintype "input"))
    )
    (net (code "17") (name "NEWRTB") (class "Default")
      (node (ref "U12") (pin "9") (pinfunction "CLK_9") (pintype "input"))
      (node (ref "U17") (pin "9") (pinfunction "CLK_9") (pintype "input"))
      (node (ref "U20") (pin "6") (pinfunction "O_6") (pintype "output"))
      (node (ref "U26") (pin "3") (pinfunction "CLK_3") (pintype "input"))
    )
    (net (code "18") (name "Net-(U1A-O)") (class "Default")
      (node (ref "U1") (pin "3") (pinfunction "O_3") (pintype "output"))
      (node (ref "U44") (pin "1") (pinfunction "I0_1") (pintype "input"))
      (node (ref "U44") (pin "10") (pinfunction "I1_10") (pintype "input"))
      (node (ref "U44") (pin "12") (pinfunction "I0_12") (pintype "input"))
      (node (ref "U44") (pin "2") (pinfunction "I1_2") (pintype "input"))
      (node (ref "U44") (pin "5") (pinfunction "I1_5") (pintype "input"))
    )
    (net (code "19") (name "Net-(U1B-I0)") (class "Default")
      (node (ref "U1") (pin "4") (pinfunction "I0_4") (pintype "input"))
      (node (ref "U43") (pin "11") (pinfunction "O_11") (pintype "output"))
      (node (ref "U43") (pin "4") (pinfunction "I0_4") (pintype "input"))
    )
    (net (code "20") (name "Net-(U1B-O)") (class "Default")
      (node (ref "U1") (pin "6") (pinfunction "O_6") (pintype "output"))
      (node (ref "U1") (pin "9") (pinfunction "I0_9") (pintype "input"))
    )
    (net (code "21") (name "Net-(U1C-I1)") (class "Default")
      (node (ref "R10") (pin "1") (pinfunction "1_1") (pintype "passive"))
      (node (ref "U1") (pin "10") (pinfunction "I1_10") (pintype "input"))
      (node (ref "U1") (pin "11") (pinfunction "O_11") (pintype "output"))
    )
    (net (code "22") (name "Net-(U2A-O)") (class "Default")
      (node (ref "U2") (pin "3") (pinfunction "O_3") (pintype "output"))
      (node (ref "U33") (pin "15") (pinfunction "A_15") (pintype "input"))
    )
    (net (code "23") (name "Net-(U2B-O)") (class "Default")
      (node (ref "U2") (pin "2") (pinfunction "O_2") (pintype "output"))
      (node (ref "U33") (pin "13") (pinfunction "C_13") (pintype "input"))
    )
    (net (code "24") (name "Net-(U2C-O)") (class "Default")
      (node (ref "U2") (pin "14") (pinfunction "O_14") (pintype "output"))
      (node (ref "U33") (pin "14") (pinfunction "B_14") (pintype "input"))
    )
    (net (code "25") (name "Net-(U10A-I1)") (class "Default")
      (node (ref "U10") (pin "13") (pinfunction "I1_13") (pintype "input"))
      (node (ref "U10") (pin "2") (pinfunction "I1_2") (pintype "input"))
      (node (ref "U10") (pin "5") (pinfunction "I1_5") (pintype "input"))
      (node (ref "U15") (pin "12") (pinfunction "I0_12") (pintype "input"))
      (node (ref "U15") (pin "13") (pinfunction "I1_13") (pintype "input"))
      (node (ref "U20") (pin "10") (pinfunction "O_10") (pintype "output"))
      (node (ref "U25") (pin "10") (pinfunction "I1_10") (pintype "input"))
      (node (ref "U6") (pin "2") (pinfunction "I1_2") (pintype "input"))
      (node (ref "U6") (pin "5") (pinfunction "I1_5") (pintype "input"))
    )
    (net (code "26") (name "Net-(U10C-I0)") (class "Default")
      (node (ref "U10") (pin "10") (pinfunction "I1_10") (pintype "input"))
      (node (ref "U10") (pin "9") (pinfunction "I0_9") (pintype "input"))
      (node (ref "U26") (pin "8") (pinfunction "~{Q}_8") (pintype "output"))
    )
    (net (code "27") (name "Net-(U11A-PRE)") (class "Default")
      (node (ref "U11") (pin "4") (pinfunction "PRE_4") (pintype "input"))
      (node (ref "U16") (pin "3") (pinfunction "O_3") (pintype "output"))
      (node (ref "U28") (pin "10") (pinfunction "I1_10") (pintype "input"))
      (node (ref "U28") (pin "11") (pinfunction "I0_11") (pintype "input"))
      (node (ref "U28") (pin "5") (pinfunction "I1_5") (pintype "input"))
      (node (ref "U28") (pin "6") (pinfunction "I0_6") (pintype "input"))
      (node (ref "U37") (pin "10") (pinfunction "I1_10") (pintype "input"))
      (node (ref "U37") (pin "11") (pinfunction "I0_11") (pintype "input"))
      (node (ref "U37") (pin "5") (pinfunction "I1_5") (pintype "input"))
      (node (ref "U37") (pin "6") (pinfunction "I0_6") (pintype "input"))
      (node (ref "U5") (pin "10") (pinfunction "I1_10") (pintype "input"))
      (node (ref "U5") (pin "11") (pinfunction "I0_11") (pintype "input"))
      (node (ref "U5") (pin "5") (pinfunction "I1_5") (pintype "input"))
      (node (ref "U5") (pin "6") (pinfunction "I0_6") (pintype "input"))
    )
    (net (code "28") (name "Net-(U11B-D)") (class "Default")
      (node (ref "U11") (pin "12") (pinfunction "D_12") (pintype "input"))
      (node (ref "U27") (pin "6") (pinfunction "A=B_O_6") (pintype "output"))
    )
    (net (code "29") (name "Net-(U11B-Q)") (class "Default")
      (node (ref "U1") (pin "12") (pinfunction "I0_12") (pintype "input"))
      (node (ref "U11") (pin "9") (pinfunction "Q_9") (pintype "output"))
    )
    (net (code "30") (name "Net-(U12A-D1)") (class "Default")
      (node (ref "U12") (pin "3") (pinfunction "D1_3") (pintype "input"))
      (node (ref "U18") (pin "14") (pinfunction "O_14") (pintype "output"))
    )
    (net (code "31") (name "Net-(U12A-D2)") (class "Default")
      (node (ref "U12") (pin "4") (pinfunction "D2_4") (pintype "input"))
      (node (ref "U18") (pin "13") (pinfunction "O_13") (pintype "output"))
    )
    (net (code "32") (name "Net-(U12A-D3)") (class "Default")
      (node (ref "U12") (pin "6") (pinfunction "D3_6") (pintype "input"))
      (node (ref "U3") (pin "2") (pinfunction "O_2") (pintype "output"))
    )
    (net (code "33") (name "Net-(U12A-D4)") (class "Default")
      (node (ref "U12") (pin "11") (pinfunction "D4_11") (pintype "input"))
      (node (ref "U3") (pin "3") (pinfunction "O_3") (pintype "output"))
    )
    (net (code "34") (name "Net-(U12A-D5)") (class "Default")
      (node (ref "U12") (pin "13") (pinfunction "D5_13") (pintype "input"))
      (node (ref "U3") (pin "14") (pinfunction "O_14") (pintype "output"))
    )
    (net (code "35") (name "Net-(U12A-D6)") (class "Default")
      (node (ref "U12") (pin "14") (pinfunction "D6_14") (pintype "input"))
      (node (ref "U3") (pin "13") (pinfunction "O_13") (pintype "output"))
    )
    (net (code "36") (name "Net-(U13A-I1)") (class "Default")
      (node (ref "R1") (pin "2") (pinfunction "2_2") (pintype "passive"))
      (node (ref "U13") (pin "5") (pinfunction "I1_5") (pintype "input"))
      (node (ref "U13") (pin "7") (pinfunction "I1_7") (pintype "input"))
      (node (ref "U31") (pin "6") (pinfunction "O_6") (pintype "output"))
      (node (ref "U7") (pin "12") (pinfunction "I6_12") (pintype "input"))
    )
    (net (code "37") (name "Net-(U13A-O)") (class "Default")
      (node (ref "U13") (pin "3") (pinfunction "O_3") (pintype "output"))
      (node (ref "U7") (pin "11") (pinfunction "I5_11") (pintype "input"))
    )
    (net (code "38") (name "Net-(U13B-O)") (class "Default")
      (node (ref "U13") (pin "2") (pinfunction "O_2") (pintype "output"))
      (node (ref "U7") (pin "4") (pinfunction "I0_4") (pintype "input"))
    )
    (net (code "39") (name "Net-(U13C-O)") (class "Default")
      (node (ref "U13") (pin "14") (pinfunction "O_14") (pintype "output"))
      (node (ref "U31") (pin "5") (pinfunction "I_5") (pintype "input"))
    )
    (net (code "40") (name "Net-(U13D-O)") (class "Default")
      (node (ref "U13") (pin "13") (pinfunction "O_13") (pintype "output"))
      (node (ref "U21") (pin "5") (pinfunction "I1_5") (pintype "input"))
    )
    (net (code "41") (name "Net-(U14C-O)") (class "Default")
      (node (ref "U14") (pin "8") (pinfunction "O_8") (pintype "output"))
      (node (ref "U23") (pin "9") (pinfunction "CLK_9") (pintype "input"))
      (node (ref "U38") (pin "9") (pinfunction "CLK_9") (pintype "input"))
    )
    (net (code "42") (name "Net-(U14D-O)") (class "Default")
      (node (ref "U1") (pin "5") (pinfunction "I1_5") (pintype "input"))
      (node (ref "U14") (pin "11") (pinfunction "O_11") (pintype "output"))
    )
    (net (code "43") (name "Net-(U15A-I1)") (class "Default")
      (node (ref "U15") (pin "10") (pinfunction "I1_10") (pintype "input"))
      (node (ref "U15") (pin "2") (pinfunction "I1_2") (pintype "input"))
      (node (ref "U15") (pin "5") (pinfunction "I1_5") (pintype "input"))
      (node (ref "U15") (pin "9") (pinfunction "I0_9") (pintype "input"))
      (node (ref "U20") (pin "8") (pinfunction "O_8") (pintype "output"))
      (node (ref "U8") (pin "10") (pinfunction "I1_10") (pintype "input"))
      (node (ref "U8") (pin "13") (pinfunction "I1_13") (pintype "input"))
      (node (ref "U8") (pin "2") (pinfunction "I1_2") (pintype "input"))
      (node (ref "U8") (pin "5") (pinfunction "I1_5") (pintype "input"))
    )
    (net (code "44") (name "Net-(U16C-O)") (class "Default")
      (node (ref "U16") (pin "14") (pinfunction "O_14") (pintype "output"))
      (node (ref "U42") (pin "3") (pinfunction "I_3") (pintype "input"))
    )
    (net (code "45") (name "Net-(U17A-D1)") (class "Default")
      (node (ref "U17") (pin "3") (pinfunction "D1_3") (pintype "input"))
      (node (ref "U9") (pin "2") (pinfunction "O_2") (pintype "output"))
    )
    (net (code "46") (name "Net-(U17A-D2)") (class "Default")
      (node (ref "U17") (pin "4") (pinfunction "D2_4") (pintype "input"))
      (node (ref "U9") (pin "3") (pinfunction "O_3") (pintype "output"))
    )
    (net (code "47") (name "Net-(U17A-D3)") (class "Default")
      (node (ref "U17") (pin "6") (pinfunction "D3_6") (pintype "input"))
      (node (ref "U9") (pin "14") (pinfunction "O_14") (pintype "output"))
    )
    (net (code "48") (name "Net-(U17A-D4)") (class "Default")
      (node (ref "U17") (pin "11") (pinfunction "D4_11") (pintype "input"))
      (node (ref "U9") (pin "13") (pinfunction "O_13") (pintype "output"))
    )
    (net (code "49") (name "Net-(U17A-D5)") (class "Default")
      (node (ref "U17") (pin "13") (pinfunction "D5_13") (pintype "input"))
      (node (ref "U18") (pin "2") (pinfunction "O_2") (pintype "output"))
    )
    (net (code "50") (name "Net-(U17A-D6)") (class "Default")
      (node (ref "U17") (pin "14") (pinfunction "D6_14") (pintype "input"))
      (node (ref "U18") (pin "3") (pinfunction "O_3") (pintype "output"))
    )
    (net (code "51") (name "Net-(U18A-I1)") (class "Default")
      (node (ref "R7") (pin "2") (pinfunction "2_2") (pintype "passive"))
      (node (ref "U18") (pin "5") (pinfunction "I1_5") (pintype "input"))
      (node (ref "U18") (pin "7") (pinfunction "I1_7") (pintype "input"))
      (node (ref "U20") (pin "2") (pinfunction "O_2") (pintype "output"))
      (node (ref "U9") (pin "10") (pinfunction "I1_10") (pintype "input"))
      (node (ref "U9") (pin "12") (pinfunction "I1_12") (pintype "input"))
      (node (ref "U9") (pin "5") (pinfunction "I1_5") (pintype "input"))
      (node (ref "U9") (pin "7") (pinfunction "I1_7") (pintype "input"))
    )
    (net (code "52") (name "Net-(U18C-I1)") (class "Default")
      (node (ref "R8") (pin "1") (pinfunction "1_1") (pintype "passive"))
      (node (ref "U18") (pin "10") (pinfunction "I1_10") (pintype "input"))
      (node (ref "U18") (pin "12") (pinfunction "I1_12") (pintype "input"))
      (node (ref "U20") (pin "4") (pinfunction "O_4") (pintype "output"))
      (node (ref "U3") (pin "10") (pinfunction "I1_10") (pintype "input"))
      (node (ref "U3") (pin "12") (pinfunction "I1_12") (pintype "input"))
      (node (ref "U3") (pin "5") (pinfunction "I1_5") (pintype "input"))
      (node (ref "U3") (pin "7") (pinfunction "I1_7") (pintype "input"))
    )
    (net (code "53") (name "Net-(U20A-I)") (class "Default")
      (node (ref "U20") (pin "1") (pinfunction "I_1") (pintype "input"))
      (node (ref "U20") (pin "12") (pinfunction "O_12") (pintype "output"))
      (node (ref "U20") (pin "3") (pinfunction "I_3") (pintype "input"))
      (node (ref "U21") (pin "4") (pinfunction "I0_4") (pintype "input"))
    )
    (net (code "54") (name "Net-(U20C-I)") (class "Default")
      (node (ref "U20") (pin "5") (pinfunction "I_5") (pintype "input"))
      (node (ref "U21") (pin "6") (pinfunction "O_6") (pintype "output"))
    )
    (net (code "55") (name "Net-(U20D-I)") (class "Default")
      (node (ref "U20") (pin "11") (pinfunction "I_11") (pintype "input"))
      (node (ref "U20") (pin "9") (pinfunction "I_9") (pintype "input"))
      (node (ref "U31") (pin "12") (pinfunction "O_12") (pintype "output"))
    )
    (net (code "56") (name "Net-(U20F-I)") (class "Default")
      (node (ref "U20") (pin "13") (pinfunction "I_13") (pintype "input"))
      (node (ref "U21") (pin "3") (pinfunction "O_3") (pintype "output"))
    )
    (net (code "57") (name "Net-(U21A-I0)") (class "Default")
      (node (ref "U21") (pin "1") (pinfunction "I0_1") (pintype "input"))
      (node (ref "U34") (pin "2") (pinfunction "O_2") (pintype "output"))
    )
    (net (code "58") (name "Net-(U21C-O)") (class "Default")
      (node (ref "U21") (pin "8") (pinfunction "O_8") (pintype "output"))
      (node (ref "U22") (pin "5") (pinfunction "I1_5") (pintype "input"))
    )
    (net (code "59") (name "Net-(U21D-I0)") (class "Default")
      (node (ref "R3") (pin "2") (pinfunction "2_2") (pintype "passive"))
      (node (ref "U21") (pin "12") (pinfunction "I0_12") (pintype "input"))
      (node (ref "U30") (pin "8") (pinfunction "O_8") (pintype "output"))
      (node (ref "U34") (pin "11") (pinfunction "I0_11") (pintype "input"))
    )
    (net (code "60") (name "Net-(U21D-O)") (class "Default")
      (node (ref "U21") (pin "11") (pinfunction "O_11") (pintype "output"))
      (node (ref "U30") (pin "11") (pinfunction "I2_11") (pintype "input"))
    )
    (net (code "61") (name "Net-(U22A-O)") (class "Default")
      (node (ref "U22") (pin "12") (pinfunction "I1_12") (pintype "input"))
      (node (ref "U22") (pin "3") (pinfunction "O_3") (pintype "output"))
    )
    (net (code "62") (name "Net-(U22B-O)") (class "Default")
      (node (ref "U22") (pin "11") (pinfunction "I0_11") (pintype "input"))
      (node (ref "U22") (pin "2") (pinfunction "O_2") (pintype "output"))
    )
    (net (code "63") (name "Net-(U22D-O)") (class "Default")
      (node (ref "U22") (pin "13") (pinfunction "O_13") (pintype "output"))
      (node (ref "U31") (pin "11") (pinfunction "I_11") (pintype "input"))
    )
    (net (code "64") (name "Net-(U23A-D1)") (class "Default")
      (node (ref "U23") (pin "3") (pinfunction "D1_3") (pintype "input"))
      (node (ref "U5") (pin "3") (pinfunction "O_3") (pintype "output"))
    )
    (net (code "65") (name "Net-(U23A-D2)") (class "Default")
      (node (ref "U23") (pin "4") (pinfunction "D2_4") (pintype "input"))
      (node (ref "U5") (pin "2") (pinfunction "O_2") (pintype "output"))
    )
    (net (code "66") (name "Net-(U23A-D3)") (class "Default")
      (node (ref "U23") (pin "6") (pinfunction "D3_6") (pintype "input"))
      (node (ref "U5") (pin "14") (pinfunction "O_14") (pintype "output"))
    )
    (net (code "67") (name "Net-(U23A-D4)") (class "Default")
      (node (ref "U23") (pin "11") (pinfunction "D4_11") (pintype "input"))
      (node (ref "U5") (pin "13") (pinfunction "O_13") (pintype "output"))
    )
    (net (code "68") (name "Net-(U23A-D5)") (class "Default")
      (node (ref "U23") (pin "13") (pinfunction "D5_13") (pintype "input"))
      (node (ref "U28") (pin "3") (pinfunction "O_3") (pintype "output"))
    )
    (net (code "69") (name "Net-(U23A-D6)") (class "Default")
      (node (ref "U23") (pin "14") (pinfunction "D6_14") (pintype "input"))
      (node (ref "U28") (pin "2") (pinfunction "O_2") (pintype "output"))
    )
    (net (code "70") (name "Net-(U24A-O)") (class "Default")
      (node (ref "U24") (pin "12") (pinfunction "I1_12") (pintype "input"))
      (node (ref "U24") (pin "3") (pinfunction "O_3") (pintype "output"))
    )
    (net (code "71") (name "Net-(U24B-O)") (class "Default")
      (node (ref "U24") (pin "2") (pinfunction "O_2") (pintype "output"))
      (node (ref "U34") (pin "7") (pinfunction "I1_7") (pintype "input"))
    )
    (net (code "72") (name "Net-(U24D-O)") (class "Default")
      (node (ref "U24") (pin "13") (pinfunction "O_13") (pintype "output"))
      (node (ref "U30") (pin "3") (pinfunction "I0_3") (pintype "input"))
      (node (ref "U30") (pin "4") (pinfunction "I1_4") (pintype "input"))
    )
    (net (code "73") (name "Net-(U25A-O)") (class "Default")
      (node (ref "R2") (pin "2") (pinfunction "2_2") (pintype "passive"))
      (node (ref "U25") (pin "3") (pinfunction "O_3") (pintype "open_collector"))
      (node (ref "U33") (pin "12") (pinfunction "D_12") (pintype "input"))
    )
    (net (code "74") (name "Net-(U25D-I0)") (class "Default")
      (node (ref "U25") (pin "12") (pinfunction "I0_12") (pintype "input"))
      (node (ref "U26") (pin "6") (pinfunction "~{Q}_6") (pintype "output"))
      (node (ref "U6") (pin "10") (pinfunction "I1_10") (pintype "input"))
      (node (ref "U6") (pin "9") (pinfunction "I0_9") (pintype "input"))
    )
    (net (code "75") (name "Net-(U26A-PRE)") (class "Default")
      (node (ref "U26") (pin "4") (pinfunction "PRE_4") (pintype "input"))
      (node (ref "U31") (pin "10") (pinfunction "O_10") (pintype "output"))
    )
    (net (code "76") (name "Net-(U26B-CLK)") (class "Default")
      (node (ref "U26") (pin "11") (pinfunction "CLK_11") (pintype "input"))
      (node (ref "U4") (pin "14") (pinfunction "O_14") (pintype "output"))
    )
    (net (code "77") (name "Net-(U26B-D)") (class "Default")
      (node (ref "U26") (pin "12") (pinfunction "D_12") (pintype "input"))
      (node (ref "U30") (pin "6") (pinfunction "O_6") (pintype "output"))
    )
    (net (code "78") (name "Net-(U26B-PRE)") (class "Default")
      (node (ref "U26") (pin "10") (pinfunction "PRE_10") (pintype "input"))
      (node (ref "U34") (pin "14") (pinfunction "O_14") (pintype "output"))
    )
    (net (code "79") (name "Net-(U27A-A0)") (class "Default")
      (node (ref "U27") (pin "10") (pinfunction "A0_10") (pintype "input"))
      (node (ref "U36") (pin "14") (pinfunction "D6_14") (pintype "input"))
      (node (ref "U36") (pin "7") (pinfunction "Q3_7") (pintype "output"))
    )
    (net (code "80") (name "Net-(U27A-A1)") (class "Default")
      (node (ref "U27") (pin "12") (pinfunction "A1_12") (pintype "input"))
      (node (ref "U36") (pin "13") (pinfunction "D5_13") (pintype "input"))
      (node (ref "U36") (pin "5") (pinfunction "Q2_5") (pintype "output"))
    )
    (net (code "81") (name "Net-(U27A-A2)") (class "Default")
      (node (ref "U27") (pin "13") (pinfunction "A2_13") (pintype "input"))
      (node (ref "U36") (pin "11") (pinfunction "D4_11") (pintype "input"))
      (node (ref "U36") (pin "2") (pinfunction "Q1_2") (pintype "output"))
    )
    (net (code "82") (name "Net-(U27A-A3)") (class "Default")
      (node (ref "U27") (pin "15") (pinfunction "A3_15") (pintype "input"))
      (node (ref "U45") (pin "12") (pinfunction "D_12") (pintype "input"))
      (node (ref "U45") (pin "5") (pinfunction "Q_5") (pintype "output"))
    )
    (net (code "83") (name "Net-(U27A-B0)") (class "Default")
      (node (ref "U27") (pin "9") (pinfunction "B0_9") (pintype "input"))
      (node (ref "U36") (pin "15") (pinfunction "Q6_15") (pintype "output"))
    )
    (net (code "84") (name "Net-(U27A-B1)") (class "Default")
      (node (ref "U27") (pin "11") (pinfunction "B1_11") (pintype "input"))
      (node (ref "U36") (pin "12") (pinfunction "Q5_12") (pintype "output"))
    )
    (net (code "85") (name "Net-(U27A-B2)") (class "Default")
      (node (ref "U27") (pin "14") (pinfunction "B2_14") (pintype "input"))
      (node (ref "U36") (pin "10") (pinfunction "Q4_10") (pintype "output"))
    )
    (net (code "86") (name "Net-(U27A-B3)") (class "Default")
      (node (ref "U27") (pin "1") (pinfunction "B3_1") (pintype "input"))
      (node (ref "U45") (pin "9") (pinfunction "Q_9") (pintype "output"))
    )
    (net (code "87") (name "Net-(U28C-O)") (class "Default")
      (node (ref "U28") (pin "14") (pinfunction "O_14") (pintype "output"))
      (node (ref "U38") (pin "3") (pinfunction "D1_3") (pintype "input"))
    )
    (net (code "88") (name "Net-(U28D-O)") (class "Default")
      (node (ref "U28") (pin "13") (pinfunction "O_13") (pintype "output"))
      (node (ref "U38") (pin "4") (pinfunction "D2_4") (pintype "input"))
    )
    (net (code "89") (name "Net-(U30A-I2)") (class "Default")
      (node (ref "R5") (pin "2") (pinfunction "2_2") (pintype "passive"))
      (node (ref "U30") (pin "13") (pinfunction "I2_13") (pintype "input"))
    )
    (net (code "90") (name "Net-(U30A-O)") (class "Default")
      (node (ref "U30") (pin "12") (pinfunction "O_12") (pintype "output"))
      (node (ref "U31") (pin "13") (pinfunction "I_13") (pintype "input"))
    )
    (net (code "91") (name "Net-(U34C-I0)") (class "Default")
      (node (ref "U34") (pin "9") (pinfunction "I0_9") (pintype "input"))
      (node (ref "U4") (pin "13") (pinfunction "O_13") (pintype "output"))
    )
    (net (code "92") (name "Net-(U35A-1Y)") (class "Default")
      (node (ref "U35") (pin "4") (pinfunction "1Y_4") (pintype "output"))
      (node (ref "U44") (pin "4") (pinfunction "I0_4") (pintype "input"))
    )
    (net (code "93") (name "Net-(U35A-2Y)") (class "Default")
      (node (ref "U35") (pin "7") (pinfunction "2Y_7") (pintype "output"))
      (node (ref "U44") (pin "9") (pinfunction "I0_9") (pintype "input"))
    )
    (net (code "94") (name "Net-(U35A-3Y)") (class "Default")
      (node (ref "U35") (pin "9") (pinfunction "3Y_9") (pintype "output"))
      (node (ref "U44") (pin "13") (pinfunction "I1_13") (pintype "input"))
    )
    (net (code "95") (name "Net-(U36A-CLK)") (class "Default")
      (node (ref "U36") (pin "9") (pinfunction "CLK_9") (pintype "input"))
      (node (ref "U43") (pin "6") (pinfunction "O_6") (pintype "output"))
      (node (ref "U45") (pin "11") (pinfunction "CLK_11") (pintype "input"))
      (node (ref "U45") (pin "3") (pinfunction "CLK_3") (pintype "input"))
    )
    (net (code "96") (name "Net-(U37A-O)") (class "Default")
      (node (ref "U37") (pin "3") (pinfunction "O_3") (pintype "output"))
      (node (ref "U38") (pin "6") (pinfunction "D3_6") (pintype "input"))
    )
    (net (code "97") (name "Net-(U37B-O)") (class "Default")
      (node (ref "U37") (pin "2") (pinfunction "O_2") (pintype "output"))
      (node (ref "U38") (pin "11") (pinfunction "D4_11") (pintype "input"))
    )
    (net (code "98") (name "Net-(U37C-O)") (class "Default")
      (node (ref "U37") (pin "14") (pinfunction "O_14") (pintype "output"))
      (node (ref "U38") (pin "13") (pinfunction "D5_13") (pintype "input"))
    )
    (net (code "99") (name "Net-(U37D-O)") (class "Default")
      (node (ref "U37") (pin "13") (pinfunction "O_13") (pintype "output"))
      (node (ref "U38") (pin "14") (pinfunction "D6_14") (pintype "input"))
    )
    (net (code "100") (name "Net-(U39A-A=B_I)") (class "Default")
      (node (ref "U39") (pin "3") (pinfunction "A=B_I_3") (pintype "input"))
      (node (ref "U40") (pin "6") (pinfunction "A=B_O_6") (pintype "output"))
    )
    (net (code "101") (name "Net-(U43A-O)") (class "Default")
      (node (ref "U43") (pin "3") (pinfunction "O_3") (pintype "output"))
      (node (ref "U43") (pin "5") (pinfunction "I1_5") (pintype "input"))
    )
    (net (code "102") (name "Net-(U43C-O)") (class "Default")
      (node (ref "U43") (pin "8") (pinfunction "O_8") (pintype "output"))
      (node (ref "U45") (pin "1") (pinfunction "CLR_1") (pintype "input"))
      (node (ref "U45") (pin "10") (pinfunction "PRE_10") (pintype "input"))
    )
    (net (code "103") (name "Net-(U45B-CLR)") (class "Default")
      (node (ref "C29") (pin "2") (pinfunction "2_2") (pintype "passive"))
      (node (ref "R10") (pin "2") (pinfunction "2_2") (pintype "passive"))
      (node (ref "U45") (pin "13") (pinfunction "CLR_13") (pintype "input"))
    )
    (net (code "104") (name "RIOT00") (class "Default")
      (node (ref "U23") (pin "2") (pinfunction "Q1_2") (pintype "output"))
      (node (ref "U40") (pin "10") (pinfunction "A0_10") (pintype "input"))
      (node (ref "U41") (pin "1") (pinfunction "I0_1") (pintype "input"))
    )
    (net (code "105") (name "RIOT01") (class "Default")
      (node (ref "U23") (pin "5") (pinfunction "Q2_5") (pintype "output"))
      (node (ref "U40") (pin "12") (pinfunction "A1_12") (pintype "input"))
      (node (ref "U41") (pin "4") (pinfunction "I0_4") (pintype "input"))
    )
    (net (code "106") (name "RIOT02") (class "Default")
      (node (ref "U23") (pin "7") (pinfunction "Q3_7") (pintype "output"))
      (node (ref "U40") (pin "13") (pinfunction "A2_13") (pintype "input"))
      (node (ref "U41") (pin "9") (pinfunction "I0_9") (pintype "input"))
    )
    (net (code "107") (name "RIOT03") (class "Default")
      (node (ref "U23") (pin "10") (pinfunction "Q4_10") (pintype "output"))
      (node (ref "U40") (pin "15") (pinfunction "A3_15") (pintype "input"))
      (node (ref "U41") (pin "12") (pinfunction "I0_12") (pintype "input"))
    )
    (net (code "108") (name "RIOT04") (class "Default")
      (node (ref "U23") (pin "12") (pinfunction "Q5_12") (pintype "output"))
      (node (ref "U32") (pin "1") (pinfunction "I0_1") (pintype "input"))
      (node (ref "U39") (pin "10") (pinfunction "A0_10") (pintype "input"))
    )
    (net (code "109") (name "RIOT05") (class "Default")
      (node (ref "U23") (pin "15") (pinfunction "Q6_15") (pintype "output"))
      (node (ref "U32") (pin "4") (pinfunction "I0_4") (pintype "input"))
      (node (ref "U39") (pin "12") (pinfunction "A1_12") (pintype "input"))
    )
    (net (code "110") (name "RIOT06") (class "Default")
      (node (ref "U29") (pin "1") (pinfunction "I0_1") (pintype "input"))
      (node (ref "U35") (pin "2") (pinfunction "1A_2") (pintype "input"))
      (node (ref "U36") (pin "3") (pinfunction "D1_3") (pintype "input"))
      (node (ref "U38") (pin "2") (pinfunction "Q1_2") (pintype "output"))
    )
    (net (code "111") (name "RIOT07") (class "Default")
      (node (ref "U29") (pin "4") (pinfunction "I0_4") (pintype "input"))
      (node (ref "U35") (pin "5") (pinfunction "2A_5") (pintype "input"))
      (node (ref "U36") (pin "4") (pinfunction "D2_4") (pintype "input"))
      (node (ref "U38") (pin "5") (pinfunction "Q2_5") (pintype "output"))
    )
    (net (code "112") (name "RIOT08") (class "Default")
      (node (ref "U29") (pin "9") (pinfunction "I0_9") (pintype "input"))
      (node (ref "U35") (pin "11") (pinfunction "3A_11") (pintype "input"))
      (node (ref "U36") (pin "6") (pinfunction "D3_6") (pintype "input"))
      (node (ref "U38") (pin "7") (pinfunction "Q3_7") (pintype "output"))
    )
    (net (code "113") (name "RIOT09") (class "Default")
      (node (ref "U35") (pin "3") (pinfunction "1B_3") (pintype "input"))
      (node (ref "U38") (pin "10") (pinfunction "Q4_10") (pintype "output"))
      (node (ref "U39") (pin "13") (pinfunction "A2_13") (pintype "input"))
    )
    (net (code "114") (name "RIOT10") (class "Default")
      (node (ref "U35") (pin "6") (pinfunction "2B_6") (pintype "input"))
      (node (ref "U38") (pin "12") (pinfunction "Q5_12") (pintype "output"))
      (node (ref "U39") (pin "15") (pinfunction "A3_15") (pintype "input"))
    )
    (net (code "115") (name "RIOT11") (class "Default")
      (node (ref "U35") (pin "10") (pinfunction "3B_10") (pintype "input"))
      (node (ref "U38") (pin "15") (pinfunction "Q6_15") (pintype "output"))
      (node (ref "U43") (pin "12") (pinfunction "I0_12") (pintype "input"))
    )
    (net (code "116") (name "RTB00") (class "Default")
      (node (ref "U17") (pin "2") (pinfunction "Q1_2") (pintype "output"))
      (node (ref "U8") (pin "1") (pinfunction "I0_1") (pintype "input"))
    )
    (net (code "117") (name "RTB01") (class "Default")
      (node (ref "U17") (pin "5") (pinfunction "Q2_5") (pintype "output"))
      (node (ref "U8") (pin "4") (pinfunction "I0_4") (pintype "input"))
    )
    (net (code "118") (name "RTB02") (class "Default")
      (node (ref "U17") (pin "7") (pinfunction "Q3_7") (pintype "output"))
      (node (ref "U8") (pin "9") (pinfunction "I0_9") (pintype "input"))
    )
    (net (code "119") (name "RTB03") (class "Default")
      (node (ref "U17") (pin "10") (pinfunction "Q4_10") (pintype "output"))
      (node (ref "U8") (pin "12") (pinfunction "I0_12") (pintype "input"))
    )
    (net (code "120") (name "RTB04") (class "Default")
      (node (ref "U15") (pin "1") (pinfunction "I0_1") (pintype "input"))
      (node (ref "U17") (pin "12") (pinfunction "Q5_12") (pintype "output"))
    )
    (net (code "121") (name "RTB05") (class "Default")
      (node (ref "U15") (pin "4") (pinfunction "I0_4") (pintype "input"))
      (node (ref "U17") (pin "15") (pinfunction "Q6_15") (pintype "output"))
    )
    (net (code "122") (name "RTB06") (class "Default")
      (node (ref "U12") (pin "2") (pinfunction "Q1_2") (pintype "output"))
      (node (ref "U6") (pin "1") (pinfunction "I0_1") (pintype "input"))
    )
    (net (code "123") (name "RTB07") (class "Default")
      (node (ref "U12") (pin "5") (pinfunction "Q2_5") (pintype "output"))
      (node (ref "U6") (pin "4") (pinfunction "I0_4") (pintype "input"))
    )
    (net (code "124") (name "RTB08") (class "Default")
      (node (ref "U12") (pin "7") (pinfunction "Q3_7") (pintype "output"))
      (node (ref "U25") (pin "9") (pinfunction "I0_9") (pintype "input"))
    )
    (net (code "125") (name "RTB09") (class "Default")
      (node (ref "U10") (pin "12") (pinfunction "I0_12") (pintype "input"))
      (node (ref "U12") (pin "10") (pinfunction "Q4_10") (pintype "output"))
    )
    (net (code "126") (name "RTB10") (class "Default")
      (node (ref "U10") (pin "1") (pinfunction "I0_1") (pintype "input"))
      (node (ref "U12") (pin "12") (pinfunction "Q5_12") (pintype "output"))
    )
    (net (code "127") (name "RTB11") (class "Default")
      (node (ref "U10") (pin "4") (pinfunction "I0_4") (pintype "input"))
      (node (ref "U12") (pin "15") (pinfunction "Q6_15") (pintype "output"))
    )
    (net (code "128") (name "SKIP") (class "Default")
      (node (ref "U1") (pin "8") (pinfunction "O_8") (pintype "output"))
      (node (ref "U32") (pin "10") (pinfunction "I1_10") (pintype "input"))
      (node (ref "U32") (pin "9") (pinfunction "I0_9") (pintype "input"))
    )
    (net (code "129") (name "TP1") (class "Default")
      (node (ref "EDGE") (pin "CD2") (pinfunction "1_CD2") (pintype "bidirectional"))
      (node (ref "U4") (pin "6") (pinfunction "I0_6") (pintype "input"))
    )
    (net (code "130") (name "TP2") (class "Default")
      (node (ref "EDGE") (pin "CE2") (pinfunction "1_CE2") (pintype "bidirectional"))
      (node (ref "U16") (pin "9") (pinfunction "I0_9") (pintype "input"))
      (node (ref "U2") (pin "12") (pinfunction "I1_12") (pintype "input"))
    )
    (net (code "131") (name "TP3") (class "Default")
      (node (ref "EDGE") (pin "CH2") (pinfunction "1_CH2") (pintype "bidirectional"))
      (node (ref "U16") (pin "12") (pinfunction "I1_12") (pintype "input"))
      (node (ref "U22") (pin "7") (pinfunction "I1_7") (pintype "input"))
    )
    (net (code "132") (name "TP4") (class "Default")
      (node (ref "EDGE") (pin "CJ2") (pinfunction "1_CJ2") (pintype "bidirectional"))
      (node (ref "U4") (pin "4") (pinfunction "I0_4") (pintype "input"))
    )
    (net (code "133") (name "UFETCH") (class "Default")
      (node (ref "U14") (pin "9") (pinfunction "I0_9") (pintype "input"))
      (node (ref "U16") (pin "2") (pinfunction "O_2") (pintype "output"))
      (node (ref "U16") (pin "4") (pinfunction "I0_4") (pintype "input"))
      (node (ref "U16") (pin "5") (pinfunction "I1_5") (pintype "input"))
      (node (ref "U43") (pin "1") (pinfunction "I0_1") (pintype "input"))
    )
    (net (code "134") (name "USER_MODE") (class "Default")
      (node (ref "EDGE") (pin "DM2") (pinfunction "1_DM2") (pintype "bidirectional"))
      (node (ref "U16") (pin "6") (pinfunction "I0_6") (pintype "input"))
      (node (ref "U34") (pin "12") (pinfunction "I1_12") (pintype "input"))
    )
    (net (code "135") (name "VCC") (class "Default")
      (node (ref "BB1") (pin "VCC1") (pinfunction "1_VCC1") (pintype "passive"))
      (node (ref "BB1") (pin "VCC2") (pinfunction "2_VCC2") (pintype "passive"))
      (node (ref "BB1") (pin "VCC3") (pinfunction "3_VCC3") (pintype "passive"))
      (node (ref "BB1") (pin "VCC4") (pinfunction "4_VCC4") (pintype "passive"))
      (node (ref "BB1") (pin "VCC5") (pinfunction "5_VCC5") (pintype "passive"))
      (node (ref "BB2") (pin "VCC1") (pinfunction "1_VCC1") (pintype "passive"))
      (node (ref "BB2") (pin "VCC2") (pinfunction "2_VCC2") (pintype "passive"))
      (node (ref "BB2") (pin "VCC3") (pinfunction "3_VCC3") (pintype "passive"))
      (node (ref "BB2") (pin "VCC4") (pinfunction "4_VCC4") (pintype "passive"))
      (node (ref "BB2") (pin "VCC5") (pinfunction "5_VCC5") (pintype "passive"))
      (node (ref "BB3") (pin "VCC1") (pinfunction "1_VCC1") (pintype "passive"))
      (node (ref "BB3") (pin "VCC2") (pinfunction "2_VCC2") (pintype "passive"))
      (node (ref "BB3") (pin "VCC3") (pinfunction "3_VCC3") (pintype "passive"))
      (node (ref "BB3") (pin "VCC4") (pinfunction "4_VCC4") (pintype "passive"))
      (node (ref "BB3") (pin "VCC5") (pinfunction "5_VCC5") (pintype "passive"))
      (node (ref "BB4") (pin "VCC1") (pinfunction "1_VCC1") (pintype "passive"))
      (node (ref "BB4") (pin "VCC2") (pinfunction "2_VCC2") (pintype "passive"))
      (node (ref "BB4") (pin "VCC3") (pinfunction "3_VCC3") (pintype "passive"))
      (node (ref "BB4") (pin "VCC4") (pinfunction "4_VCC4") (pintype "passive"))
      (node (ref "BB4") (pin "VCC5") (pinfunction "5_VCC5") (pintype "passive"))
      (node (ref "BB5") (pin "VCC1") (pinfunction "1_VCC1") (pintype "passive"))
      (node (ref "BB5") (pin "VCC2") (pinfunction "2_VCC2") (pintype "passive"))
      (node (ref "BB5") (pin "VCC3") (pinfunction "3_VCC3") (pintype "passive"))
      (node (ref "BB5") (pin "VCC4") (pinfunction "4_VCC4") (pintype "passive"))
      (node (ref "BB5") (pin "VCC5") (pinfunction "5_VCC5") (pintype "passive"))
      (node (ref "BB6") (pin "VCC1") (pinfunction "1_VCC1") (pintype "passive"))
      (node (ref "BB6") (pin "VCC2") (pinfunction "2_VCC2") (pintype "passive"))
      (node (ref "BB6") (pin "VCC3") (pinfunction "3_VCC3") (pintype "passive"))
      (node (ref "BB6") (pin "VCC4") (pinfunction "4_VCC4") (pintype "passive"))
      (node (ref "BB6") (pin "VCC5") (pinfunction "5_VCC5") (pintype "passive"))
      (node (ref "BB7") (pin "VCC1") (pinfunction "1_VCC1") (pintype "passive"))
      (node (ref "BB7") (pin "VCC2") (pinfunction "2_VCC2") (pintype "passive"))
      (node (ref "BB7") (pin "VCC3") (pinfunction "3_VCC3") (pintype "passive"))
      (node (ref "BB7") (pin "VCC4") (pinfunction "4_VCC4") (pintype "passive"))
      (node (ref "BB7") (pin "VCC5") (pinfunction "5_VCC5") (pintype "passive"))
      (node (ref "BB8") (pin "VCC1") (pinfunction "1_VCC1") (pintype "passive"))
      (node (ref "BB8") (pin "VCC2") (pinfunction "2_VCC2") (pintype "passive"))
      (node (ref "BB8") (pin "VCC3") (pinfunction "3_VCC3") (pintype "passive"))
      (node (ref "BB8") (pin "VCC4") (pinfunction "4_VCC4") (pintype "passive"))
      (node (ref "BB8") (pin "VCC5") (pinfunction "5_VCC5") (pintype "passive"))
      (node (ref "C1") (pin "1") (pinfunction "1_1") (pintype "passive"))
      (node (ref "C10") (pin "1") (pinfunction "1_1") (pintype "passive"))
      (node (ref "C11") (pin "1") (pinfunction "1_1") (pintype "passive"))
      (node (ref "C12") (pin "1") (pinfunction "1_1") (pintype "passive"))
      (node (ref "C13") (pin "1") (pinfunction "1_1") (pintype "passive"))
      (node (ref "C14") (pin "1") (pinfunction "1_1") (pintype "passive"))
      (node (ref "C15") (pin "1") (pinfunction "1_1") (pintype "passive"))
      (node (ref "C16") (pin "1") (pinfunction "1_1") (pintype "passive"))
      (node (ref "C17") (pin "1") (pinfunction "1_1") (pintype "passive"))
      (node (ref "C18") (pin "1") (pinfunction "1_1") (pintype "passive"))
      (node (ref "C19") (pin "1") (pinfunction "1_1") (pintype "passive"))
      (node (ref "C2") (pin "1") (pinfunction "1_1") (pintype "passive"))
      (node (ref "C20") (pin "1") (pinfunction "1_1") (pintype "passive"))
      (node (ref "C21") (pin "1") (pinfunction "1_1") (pintype "passive"))
      (node (ref "C22") (pin "1") (pinfunction "1_1") (pintype "passive"))
      (node (ref "C23") (pin "1") (pinfunction "1_1") (pintype "passive"))
      (node (ref "C24") (pin "1") (pinfunction "1_1") (pintype "passive"))
      (node (ref "C25") (pin "1") (pinfunction "1_1") (pintype "passive"))
      (node (ref "C26") (pin "1") (pinfunction "1_1") (pintype "passive"))
      (node (ref "C27") (pin "1") (pinfunction "1_1") (pintype "passive"))
      (node (ref "C28") (pin "1") (pinfunction "1_1") (pintype "passive"))
      (node (ref "C29") (pin "1") (pinfunction "1_1") (pintype "passive"))
      (node (ref "C3") (pin "1") (pinfunction "1_1") (pintype "passive"))
      (node (ref "C4") (pin "1") (pinfunction "1_1") (pintype "passive"))
      (node (ref "C46") (pin "+") (pinfunction "+_+") (pintype "passive"))
      (node (ref "C47") (pin "+") (pinfunction "+_+") (pintype "passive"))
      (node (ref "C48") (pin "+") (pinfunction "+_+") (pintype "passive"))
      (node (ref "C5") (pin "1") (pinfunction "1_1") (pintype "passive"))
      (node (ref "C6") (pin "1") (pinfunction "1_1") (pintype "passive"))
      (node (ref "C7") (pin "1") (pinfunction "1_1") (pintype "passive"))
      (node (ref "C8") (pin "1") (pinfunction "1_1") (pintype "passive"))
      (node (ref "C9") (pin "1") (pinfunction "1_1") (pintype "passive"))
      (node (ref "EDGE") (pin "AA2") (pinfunction "1_AA2") (pintype "bidirectional"))
      (node (ref "EDGE") (pin "BA2") (pinfunction "1_BA2") (pintype "bidirectional"))
      (node (ref "EDGE") (pin "CA2") (pinfunction "1_CA2") (pintype "bidirectional"))
      (node (ref "R1") (pin "1") (pinfunction "1_1") (pintype "passive"))
      (node (ref "R2") (pin "1") (pinfunction "1_1") (pintype "passive"))
      (node (ref "R3") (pin "1") (pinfunction "1_1") (pintype "passive"))
      (node (ref "R4") (pin "1") (pinfunction "1_1") (pintype "passive"))
      (node (ref "R5") (pin "1") (pinfunction "1_1") (pintype "passive"))
      (node (ref "R6") (pin "1") (pinfunction "1_1") (pintype "passive"))
      (node (ref "R7") (pin "1") (pinfunction "1_1") (pintype "passive"))
      (node (ref "R8") (pin "2") (pinfunction "2_2") (pintype "passive"))
      (node (ref "R9") (pin "2") (pinfunction "2_2") (pintype "passive"))
    )
    (net (code "136") (name "unconnected-(U11A-~{Q}-Pad6)") (class "Default")
      (node (ref "U11") (pin "6") (pinfunction "~{Q}_6") (pintype "output"))
    )
    (net (code "137") (name "unconnected-(U11B-~{Q}-Pad8)") (class "Default")
      (node (ref "U11") (pin "8") (pinfunction "~{Q}_8") (pintype "output"))
    )
    (net (code "138") (name "unconnected-(U26A-Q-Pad5)") (class "Default")
      (node (ref "U26") (pin "5") (pinfunction "Q_5") (pintype "output"))
    )
    (net (code "139") (name "unconnected-(U26B-Q-Pad9)") (class "Default")
      (node (ref "U26") (pin "9") (pinfunction "Q_9") (pintype "output"))
    )
    (net (code "140") (name "unconnected-(U27A-A<B_O-Pad7)") (class "Default")
      (node (ref "U27") (pin "7") (pinfunction "A<B_O_7") (pintype "output"))
    )
    (net (code "141") (name "unconnected-(U27A-A>B_O-Pad5)") (class "Default")
      (node (ref "U27") (pin "5") (pinfunction "A>B_O_5") (pintype "output"))
    )
    (net (code "142") (name "unconnected-(U33A-O8-Pad10)") (class "Default")
      (node (ref "U33") (pin "10") (pinfunction "O8_10") (pintype "output"))
    )
    (net (code "143") (name "unconnected-(U33A-O9-Pad11)") (class "Default")
      (node (ref "U33") (pin "11") (pinfunction "O9_11") (pintype "output"))
    )
    (net (code "144") (name "unconnected-(U35A-4A-Pad14)") (class "Default")
      (node (ref "U35") (pin "14") (pinfunction "4A_14") (pintype "input"))
    )
    (net (code "145") (name "unconnected-(U35A-4B-Pad13)") (class "Default")
      (node (ref "U35") (pin "13") (pinfunction "4B_13") (pintype "input"))
    )
    (net (code "146") (name "unconnected-(U35A-4Y-Pad12)") (class "Default")
      (node (ref "U35") (pin "12") (pinfunction "4Y_12") (pintype "output"))
    )
    (net (code "147") (name "unconnected-(U39A-A<B_O-Pad7)") (class "Default")
      (node (ref "U39") (pin "7") (pinfunction "A<B_O_7") (pintype "output"))
    )
    (net (code "148") (name "unconnected-(U39A-A>B_O-Pad5)") (class "Default")
      (node (ref "U39") (pin "5") (pinfunction "A>B_O_5") (pintype "output"))
    )
    (net (code "149") (name "unconnected-(U40A-A<B_O-Pad7)") (class "Default")
      (node (ref "U40") (pin "7") (pinfunction "A<B_O_7") (pintype "output"))
    )
    (net (code "150") (name "unconnected-(U40A-A>B_O-Pad5)") (class "Default")
      (node (ref "U40") (pin "5") (pinfunction "A>B_O_5") (pintype "output"))
    )
    (net (code "151") (name "unconnected-(U45A-~{Q}-Pad6)") (class "Default")
      (node (ref "U45") (pin "6") (pinfunction "~{Q}_6") (pintype "output"))
    )
    (net (code "152") (name "unconnected-(U45B-~{Q}-Pad8)") (class "Default")
      (node (ref "U45") (pin "8") (pinfunction "~{Q}_8") (pintype "output"))
    )
    (net (code "153") (name "~{C0}") (class "Default")
      (node (ref "EDGE") (pin "CE1") (pinfunction "1_CE1") (pintype "bidirectional"))
      (node (ref "U15") (pin "8") (pinfunction "O_8") (pintype "open_collector"))
      (node (ref "U29") (pin "11") (pinfunction "O_11") (pintype "open_collector"))
    )
    (net (code "154") (name "~{C1}") (class "Default")
      (node (ref "EDGE") (pin "CH1") (pinfunction "1_CH1") (pintype "bidirectional"))
      (node (ref "U15") (pin "11") (pinfunction "O_11") (pintype "open_collector"))
      (node (ref "U44") (pin "3") (pinfunction "O_3") (pintype "open_collector"))
    )
    (net (code "155") (name "~{DATA00}") (class "Default")
      (node (ref "EDGE") (pin "AR1") (pinfunction "1_AR1") (pintype "bidirectional"))
      (node (ref "U41") (pin "3") (pinfunction "O_3") (pintype "open_collector"))
      (node (ref "U8") (pin "3") (pinfunction "O_3") (pintype "open_collector"))
    )
    (net (code "156") (name "~{DATA01}") (class "Default")
      (node (ref "EDGE") (pin "AS1") (pinfunction "1_AS1") (pintype "bidirectional"))
      (node (ref "U41") (pin "6") (pinfunction "O_6") (pintype "open_collector"))
      (node (ref "U8") (pin "6") (pinfunction "O_6") (pintype "open_collector"))
    )
    (net (code "157") (name "~{DATA02}") (class "Default")
      (node (ref "EDGE") (pin "AU1") (pinfunction "1_AU1") (pintype "bidirectional"))
      (node (ref "U41") (pin "8") (pinfunction "O_8") (pintype "open_collector"))
      (node (ref "U8") (pin "8") (pinfunction "O_8") (pintype "open_collector"))
    )
    (net (code "158") (name "~{DATA03}") (class "Default")
      (node (ref "EDGE") (pin "AV1") (pinfunction "1_AV1") (pintype "bidirectional"))
      (node (ref "U41") (pin "11") (pinfunction "O_11") (pintype "open_collector"))
      (node (ref "U8") (pin "11") (pinfunction "O_11") (pintype "open_collector"))
    )
    (net (code "159") (name "~{DATA04}") (class "Default")
      (node (ref "EDGE") (pin "BR1") (pinfunction "1_BR1") (pintype "bidirectional"))
      (node (ref "U15") (pin "3") (pinfunction "O_3") (pintype "open_collector"))
      (node (ref "U32") (pin "3") (pinfunction "O_3") (pintype "open_collector"))
    )
    (net (code "160") (name "~{DATA05}") (class "Default")
      (node (ref "EDGE") (pin "BS1") (pinfunction "1_BS1") (pintype "bidirectional"))
      (node (ref "U15") (pin "6") (pinfunction "O_6") (pintype "open_collector"))
      (node (ref "U32") (pin "6") (pinfunction "O_6") (pintype "open_collector"))
    )
    (net (code "161") (name "~{DATA06}") (class "Default")
      (node (ref "EDGE") (pin "BU1") (pinfunction "1_BU1") (pintype "bidirectional"))
      (node (ref "U29") (pin "3") (pinfunction "O_3") (pintype "open_collector"))
      (node (ref "U6") (pin "3") (pinfunction "O_3") (pintype "open_collector"))
    )
    (net (code "162") (name "~{DATA07}") (class "Default")
      (node (ref "EDGE") (pin "BV1") (pinfunction "1_BV1") (pintype "bidirectional"))
      (node (ref "U29") (pin "6") (pinfunction "O_6") (pintype "open_collector"))
      (node (ref "U6") (pin "6") (pinfunction "O_6") (pintype "open_collector"))
    )
    (net (code "163") (name "~{DATA08}") (class "Default")
      (node (ref "EDGE") (pin "DR1") (pinfunction "1_DR1") (pintype "bidirectional"))
      (node (ref "U25") (pin "8") (pinfunction "O_8") (pintype "open_collector"))
      (node (ref "U29") (pin "8") (pinfunction "O_8") (pintype "open_collector"))
    )
    (net (code "164") (name "~{DATA09}") (class "Default")
      (node (ref "EDGE") (pin "DS1") (pinfunction "1_DS1") (pintype "bidirectional"))
      (node (ref "U10") (pin "11") (pinfunction "O_11") (pintype "open_collector"))
      (node (ref "U44") (pin "6") (pinfunction "O_6") (pintype "open_collector"))
    )
    (net (code "165") (name "~{DATA10}") (class "Default")
      (node (ref "EDGE") (pin "DU1") (pinfunction "1_DU1") (pintype "bidirectional"))
      (node (ref "U10") (pin "3") (pinfunction "O_3") (pintype "open_collector"))
      (node (ref "U44") (pin "8") (pinfunction "O_8") (pintype "open_collector"))
    )
    (net (code "166") (name "~{DATA11}") (class "Default")
      (node (ref "EDGE") (pin "DV1") (pinfunction "1_DV1") (pintype "bidirectional"))
      (node (ref "U10") (pin "6") (pinfunction "O_6") (pintype "open_collector"))
      (node (ref "U44") (pin "11") (pinfunction "O_11") (pintype "open_collector"))
    )
    (net (code "167") (name "~{ECDF}") (class "Default")
      (node (ref "U33") (pin "4") (pinfunction "O3_4") (pintype "output"))
      (node (ref "U42") (pin "11") (pinfunction "I_11") (pintype "input"))
    )
    (net (code "168") (name "~{ECTF}") (class "Default")
      (node (ref "U21") (pin "9") (pinfunction "I0_9") (pintype "input"))
      (node (ref "U33") (pin "3") (pinfunction "O2_3") (pintype "output"))
    )
    (net (code "169") (name "~{ERIOT}") (class "Default")
      (node (ref "U1") (pin "1") (pinfunction "I0_1") (pintype "input"))
      (node (ref "U33") (pin "7") (pinfunction "O6_7") (pintype "output"))
      (node (ref "U42") (pin "13") (pinfunction "I_13") (pintype "input"))
    )
    (net (code "170") (name "~{ERTB}") (class "Default")
      (node (ref "U30") (pin "1") (pinfunction "I0_1") (pintype "input"))
      (node (ref "U30") (pin "2") (pinfunction "I1_2") (pintype "input"))
      (node (ref "U33") (pin "5") (pinfunction "O4_5") (pintype "output"))
    )
    (net (code "171") (name "~{ESKP}") (class "Default")
      (node (ref "U31") (pin "3") (pinfunction "I_3") (pintype "input"))
      (node (ref "U33") (pin "2") (pinfunction "O1_2") (pintype "output"))
    )
    (net (code "172") (name "~{ESME}") (class "Default")
      (node (ref "U33") (pin "6") (pinfunction "O5_6") (pintype "output"))
      (node (ref "U42") (pin "9") (pinfunction "I_9") (pintype "input"))
    )
    (net (code "173") (name "~{ETDS}") (class "Default")
      (node (ref "U21") (pin "10") (pinfunction "I1_10") (pintype "input"))
      (node (ref "U30") (pin "10") (pinfunction "I1_10") (pintype "input"))
      (node (ref "U33") (pin "1") (pinfunction "O0_1") (pintype "output"))
      (node (ref "U43") (pin "10") (pinfunction "I1_10") (pintype "input"))
    )
    (net (code "174") (name "~{ETEN}") (class "Default")
      (node (ref "U21") (pin "13") (pinfunction "I1_13") (pintype "input"))
      (node (ref "U33") (pin "9") (pinfunction "O7_9") (pintype "output"))
    )
    (net (code "175") (name "~{E}") (class "Default")
      (node (ref "EDGE") (pin "DL2") (pinfunction "1_DL2") (pintype "bidirectional"))
      (node (ref "U4") (pin "10") (pinfunction "I1_10") (pintype "input"))
      (node (ref "U4") (pin "11") (pinfunction "I0_11") (pintype "input"))
    )
    (net (code "176") (name "~{F}") (class "Default")
      (node (ref "EDGE") (pin "DJ2") (pinfunction "1_DJ2") (pintype "bidirectional"))
      (node (ref "U13") (pin "11") (pinfunction "I0_11") (pintype "input"))
      (node (ref "U16") (pin "7") (pinfunction "I1_7") (pintype "input"))
    )
    (net (code "177") (name "~{INITIALIZE}") (class "Default")
      (node (ref "U12") (pin "1") (pinfunction "CLR_1") (pintype "input"))
      (node (ref "U17") (pin "1") (pinfunction "CLR_1") (pintype "input"))
      (node (ref "U22") (pin "14") (pinfunction "O_14") (pintype "output"))
      (node (ref "U23") (pin "1") (pinfunction "CLR_1") (pintype "input"))
      (node (ref "U30") (pin "9") (pinfunction "I0_9") (pintype "input"))
      (node (ref "U31") (pin "9") (pinfunction "I_9") (pintype "input"))
      (node (ref "U36") (pin "1") (pinfunction "CLR_1") (pintype "input"))
      (node (ref "U38") (pin "1") (pinfunction "CLR_1") (pintype "input"))
      (node (ref "U43") (pin "9") (pinfunction "I0_9") (pintype "input"))
    )
    (net (code "178") (name "~{INTERNAL_IO}") (class "Default")
      (node (ref "EDGE") (pin "CL1") (pinfunction "1_CL1") (pintype "bidirectional"))
      (node (ref "U25") (pin "6") (pinfunction "O_6") (pintype "open_collector"))
    )
    (net (code "179") (name "~{INT_RQST}") (class "Default")
      (node (ref "EDGE") (pin "CP1") (pinfunction "1_CP1") (pintype "bidirectional"))
      (node (ref "U6") (pin "8") (pinfunction "O_8") (pintype "open_collector"))
    )
    (net (code "180") (name "~{IO_PAUSE}") (class "Default")
      (node (ref "EDGE") (pin "CD1") (pinfunction "1_CD1") (pintype "bidirectional"))
      (node (ref "U13") (pin "9") (pinfunction "I0_9") (pintype "input"))
    )
    (net (code "181") (name "~{IR0}") (class "Default")
      (node (ref "EDGE") (pin "DD2") (pinfunction "1_DD2") (pintype "bidirectional"))
      (node (ref "U24") (pin "11") (pinfunction "I0_11") (pintype "input"))
    )
    (net (code "182") (name "~{IR1}") (class "Default")
      (node (ref "EDGE") (pin "DE2") (pinfunction "1_DE2") (pintype "bidirectional"))
      (node (ref "U24") (pin "4") (pinfunction "I0_4") (pintype "input"))
    )
    (net (code "183") (name "~{MA00}") (class "Default")
      (node (ref "EDGE") (pin "AD1") (pinfunction "1_AD1") (pintype "bidirectional"))
      (node (ref "U9") (pin "6") (pinfunction "I0_6") (pintype "input"))
    )
    (net (code "184") (name "~{MA01}") (class "Default")
      (node (ref "EDGE") (pin "AE1") (pinfunction "1_AE1") (pintype "bidirectional"))
      (node (ref "U9") (pin "4") (pinfunction "I0_4") (pintype "input"))
    )
    (net (code "185") (name "~{MA02}") (class "Default")
      (node (ref "EDGE") (pin "AH1") (pinfunction "1_AH1") (pintype "bidirectional"))
      (node (ref "U9") (pin "9") (pinfunction "I0_9") (pintype "input"))
    )
    (net (code "186") (name "~{MA03}") (class "Default")
      (node (ref "EDGE") (pin "AJ1") (pinfunction "1_AJ1") (pintype "bidirectional"))
      (node (ref "U9") (pin "11") (pinfunction "I0_11") (pintype "input"))
    )
    (net (code "187") (name "~{MA04}") (class "Default")
      (node (ref "EDGE") (pin "BD1") (pinfunction "1_BD1") (pintype "bidirectional"))
      (node (ref "U18") (pin "6") (pinfunction "I0_6") (pintype "input"))
    )
    (net (code "188") (name "~{MA05}") (class "Default")
      (node (ref "EDGE") (pin "BE1") (pinfunction "1_BE1") (pintype "bidirectional"))
      (node (ref "U18") (pin "4") (pinfunction "I0_4") (pintype "input"))
    )
    (net (code "189") (name "~{MA06}") (class "Default")
      (node (ref "EDGE") (pin "BH1") (pinfunction "1_BH1") (pintype "bidirectional"))
      (node (ref "U18") (pin "9") (pinfunction "I0_9") (pintype "input"))
    )
    (net (code "190") (name "~{MA07}") (class "Default")
      (node (ref "EDGE") (pin "BJ1") (pinfunction "1_BJ1") (pintype "bidirectional"))
      (node (ref "U18") (pin "11") (pinfunction "I0_11") (pintype "input"))
    )
    (net (code "191") (name "~{MA08}") (class "Default")
      (node (ref "EDGE") (pin "DD1") (pinfunction "1_DD1") (pintype "bidirectional"))
      (node (ref "U3") (pin "6") (pinfunction "I0_6") (pintype "input"))
    )
    (net (code "192") (name "~{MA09}") (class "Default")
      (node (ref "EDGE") (pin "DE1") (pinfunction "1_DE1") (pintype "bidirectional"))
      (node (ref "U3") (pin "4") (pinfunction "I0_4") (pintype "input"))
    )
    (net (code "193") (name "~{MA10}") (class "Default")
      (node (ref "EDGE") (pin "DH1") (pinfunction "1_DH1") (pintype "bidirectional"))
      (node (ref "U3") (pin "9") (pinfunction "I0_9") (pintype "input"))
    )
    (net (code "194") (name "~{MA11}") (class "Default")
      (node (ref "EDGE") (pin "DJ1") (pinfunction "1_DJ1") (pintype "bidirectional"))
      (node (ref "U3") (pin "11") (pinfunction "I0_11") (pintype "input"))
    )
    (net (code "195") (name "~{MD00}") (class "Default")
      (node (ref "EDGE") (pin "AK1") (pinfunction "1_AK1") (pintype "bidirectional"))
      (node (ref "U34") (pin "6") (pinfunction "I0_6") (pintype "input"))
      (node (ref "U5") (pin "4") (pinfunction "I0_4") (pintype "input"))
    )
    (net (code "196") (name "~{MD01}") (class "Default")
      (node (ref "EDGE") (pin "AL1") (pinfunction "1_AL1") (pintype "bidirectional"))
      (node (ref "U24") (pin "6") (pinfunction "I0_6") (pintype "input"))
      (node (ref "U5") (pin "7") (pinfunction "I1_7") (pintype "input"))
    )
    (net (code "197") (name "~{MD02}") (class "Default")
      (node (ref "EDGE") (pin "AM1") (pinfunction "1_AM1") (pintype "bidirectional"))
      (node (ref "U5") (pin "9") (pinfunction "I0_9") (pintype "input"))
    )
    (net (code "198") (name "~{MD03}") (class "Default")
      (node (ref "EDGE") (pin "AP1") (pinfunction "1_AP1") (pintype "bidirectional"))
      (node (ref "U13") (pin "6") (pinfunction "I0_6") (pintype "input"))
      (node (ref "U5") (pin "12") (pinfunction "I1_12") (pintype "input"))
    )
    (net (code "199") (name "~{MD04}") (class "Default")
      (node (ref "EDGE") (pin "BK1") (pinfunction "1_BK1") (pintype "bidirectional"))
      (node (ref "U28") (pin "4") (pinfunction "I0_4") (pintype "input"))
      (node (ref "U7") (pin "5") (pinfunction "I1_5") (pintype "input"))
    )
    (net (code "200") (name "~{MD05}") (class "Default")
      (node (ref "EDGE") (pin "BL1") (pinfunction "1_BL1") (pintype "bidirectional"))
      (node (ref "U28") (pin "7") (pinfunction "I1_7") (pintype "input"))
      (node (ref "U7") (pin "6") (pinfunction "I2_6") (pintype "input"))
    )
    (net (code "201") (name "~{MD06}") (class "Default")
      (node (ref "EDGE") (pin "BM1") (pinfunction "1_BM1") (pintype "bidirectional"))
      (node (ref "U28") (pin "9") (pinfunction "I0_9") (pintype "input"))
      (node (ref "U7") (pin "9") (pinfunction "I3_9") (pintype "input"))
    )
    (net (code "202") (name "~{MD07}") (class "Default")
      (node (ref "EDGE") (pin "BP1") (pinfunction "1_BP1") (pintype "bidirectional"))
      (node (ref "U28") (pin "12") (pinfunction "I1_12") (pintype "input"))
      (node (ref "U7") (pin "10") (pinfunction "I4_10") (pintype "input"))
    )
    (net (code "203") (name "~{MD08}") (class "Default")
      (node (ref "EDGE") (pin "DK1") (pinfunction "1_DK1") (pintype "bidirectional"))
      (node (ref "U13") (pin "4") (pinfunction "I0_4") (pintype "input"))
      (node (ref "U37") (pin "4") (pinfunction "I0_4") (pintype "input"))
    )
    (net (code "204") (name "~{MD09}") (class "Default")
      (node (ref "EDGE") (pin "DL1") (pinfunction "1_DL1") (pintype "bidirectional"))
      (node (ref "U2") (pin "7") (pinfunction "I1_7") (pintype "input"))
      (node (ref "U37") (pin "7") (pinfunction "I1_7") (pintype "input"))
    )
    (net (code "205") (name "~{MD10}") (class "Default")
      (node (ref "EDGE") (pin "DM1") (pinfunction "1_DM1") (pintype "bidirectional"))
      (node (ref "U2") (pin "9") (pinfunction "I0_9") (pintype "input"))
      (node (ref "U37") (pin "9") (pinfunction "I0_9") (pintype "input"))
    )
    (net (code "206") (name "~{MD11}") (class "Default")
      (node (ref "EDGE") (pin "DP1") (pinfunction "1_DP1") (pintype "bidirectional"))
      (node (ref "U2") (pin "4") (pinfunction "I0_4") (pintype "input"))
      (node (ref "U37") (pin "12") (pinfunction "I1_12") (pintype "input"))
    )
    (net (code "207") (name "~{MD_DIR}") (class "Default")
      (node (ref "EDGE") (pin "AK2") (pinfunction "1_AK2") (pintype "bidirectional"))
      (node (ref "U10") (pin "8") (pinfunction "O_8") (pintype "open_collector"))
    )
    (net (code "208") (name "~{SKIP}") (class "Default")
      (node (ref "EDGE") (pin "CS1") (pinfunction "1_CS1") (pintype "bidirectional"))
      (node (ref "U25") (pin "11") (pinfunction "O_11") (pintype "open_collector"))
      (node (ref "U32") (pin "8") (pinfunction "O_8") (pintype "open_collector"))
    )
    (net (code "209") (name "~{TP1}") (class "Default")
      (node (ref "U4") (pin "2") (pinfunction "O_2") (pintype "output"))
      (node (ref "U4") (pin "9") (pinfunction "I0_9") (pintype "input"))
    )
    (net (code "210") (name "~{TP2}") (class "Default")
      (node (ref "U13") (pin "12") (pinfunction "I1_12") (pintype "input"))
      (node (ref "U2") (pin "13") (pinfunction "O_13") (pintype "output"))
    )
    (net (code "211") (name "~{TP3}") (class "Default")
      (node (ref "U16") (pin "13") (pinfunction "O_13") (pintype "output"))
      (node (ref "U42") (pin "5") (pinfunction "I_5") (pintype "input"))
    )
    (net (code "212") (name "~{TP4}") (class "Default")
      (node (ref "U4") (pin "12") (pinfunction "I1_12") (pintype "input"))
      (node (ref "U4") (pin "3") (pinfunction "O_3") (pintype "output"))
    )
  )
)
